# ESC.net
KiCad netlist of a schematic drawn in Altium Designer
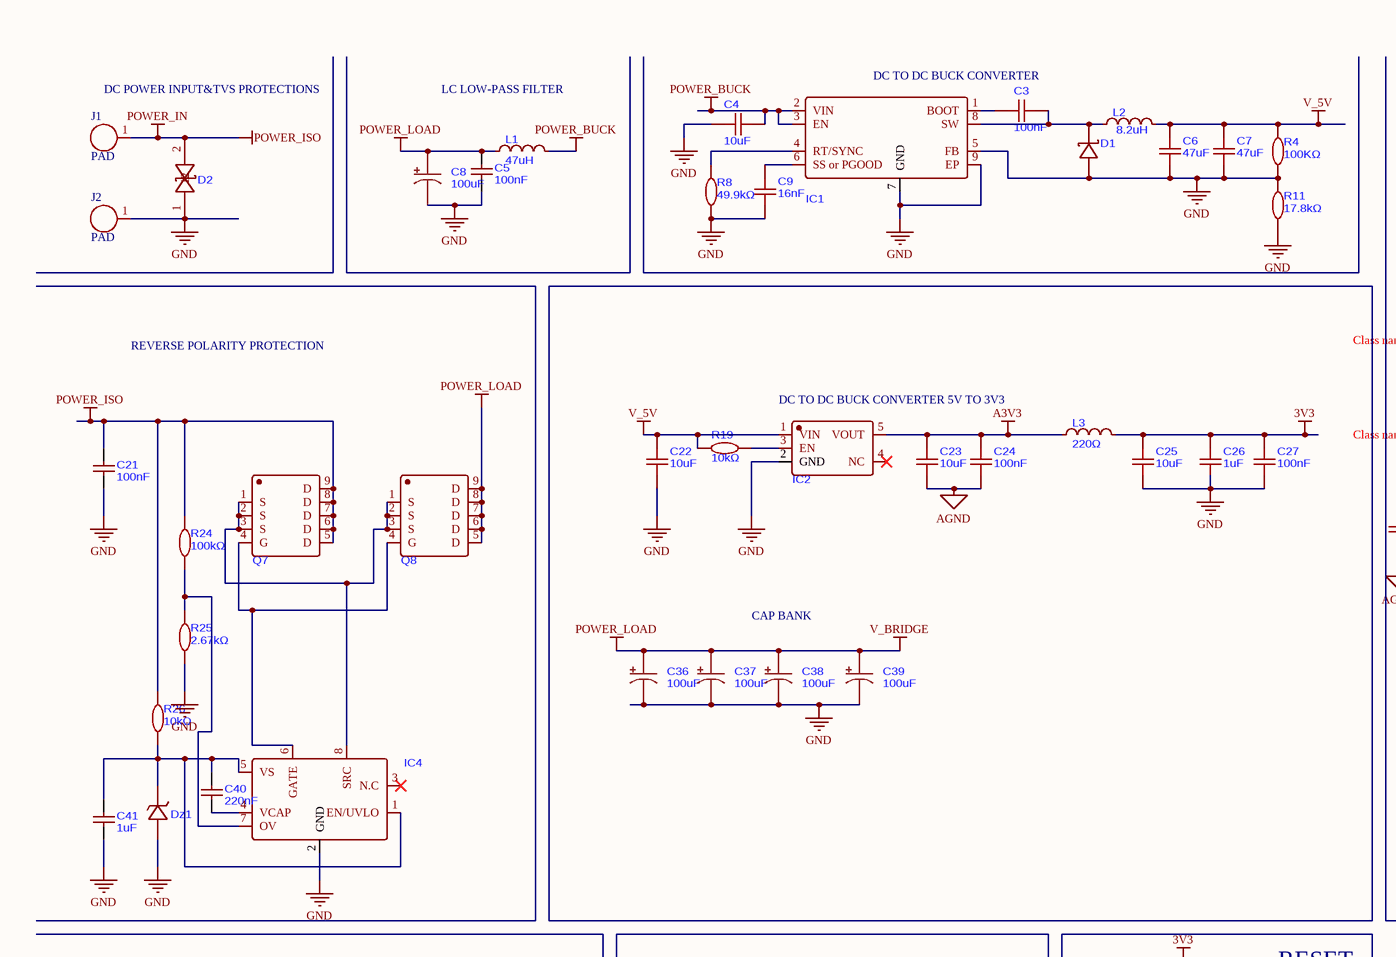
[diagram p0: ESC.SchDoc, top left]
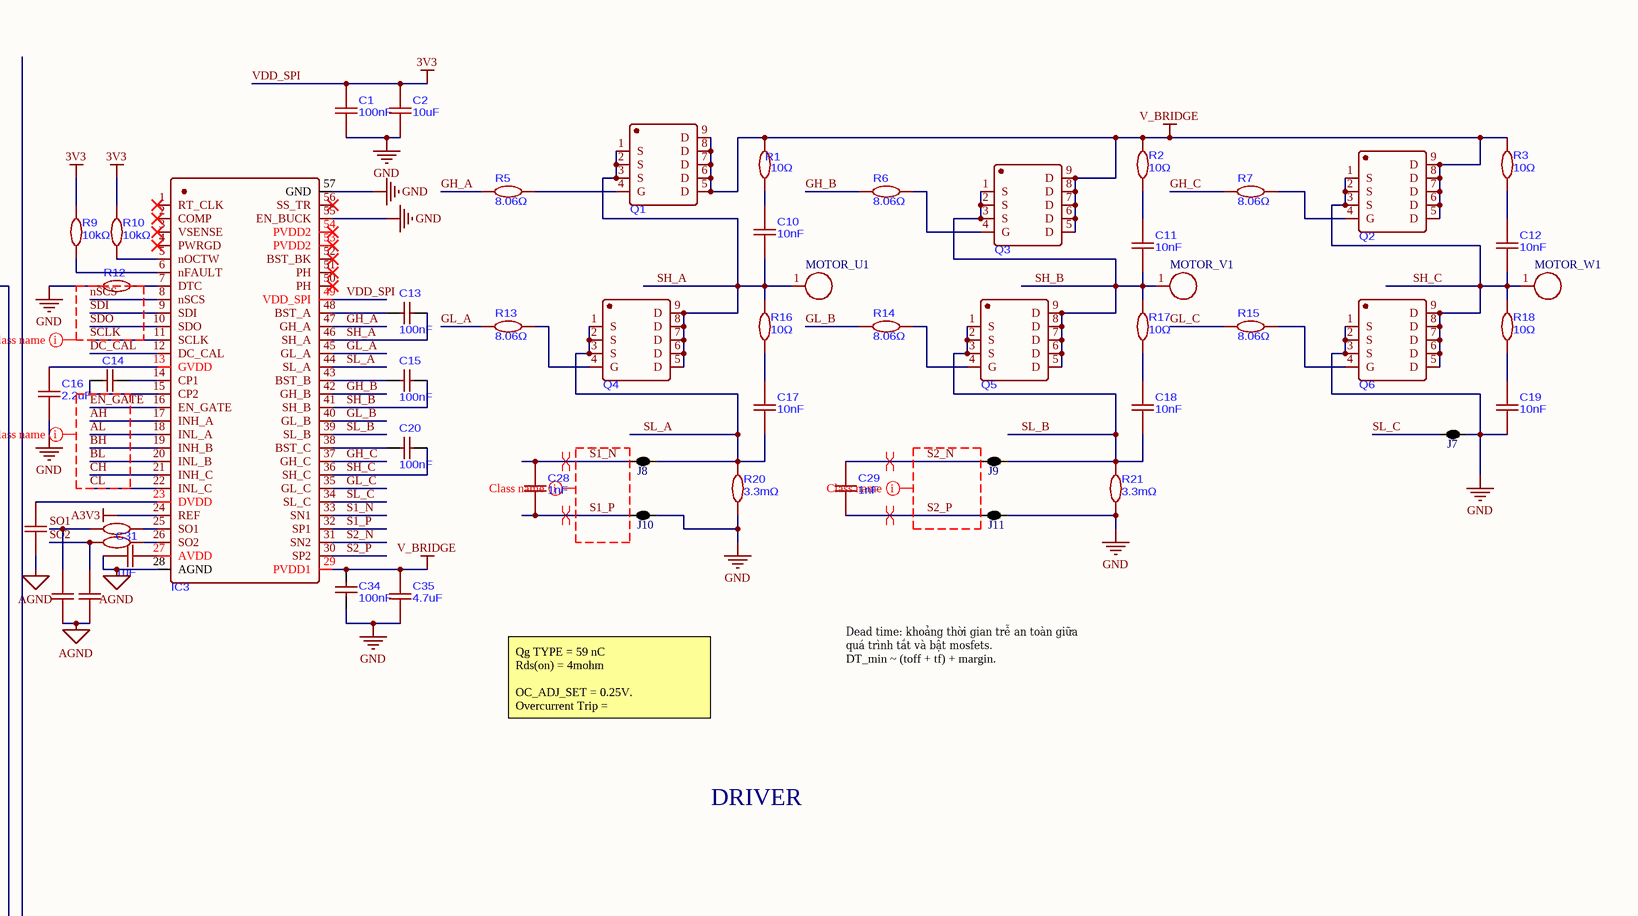
[diagram p1: ESC.SchDoc, top right]
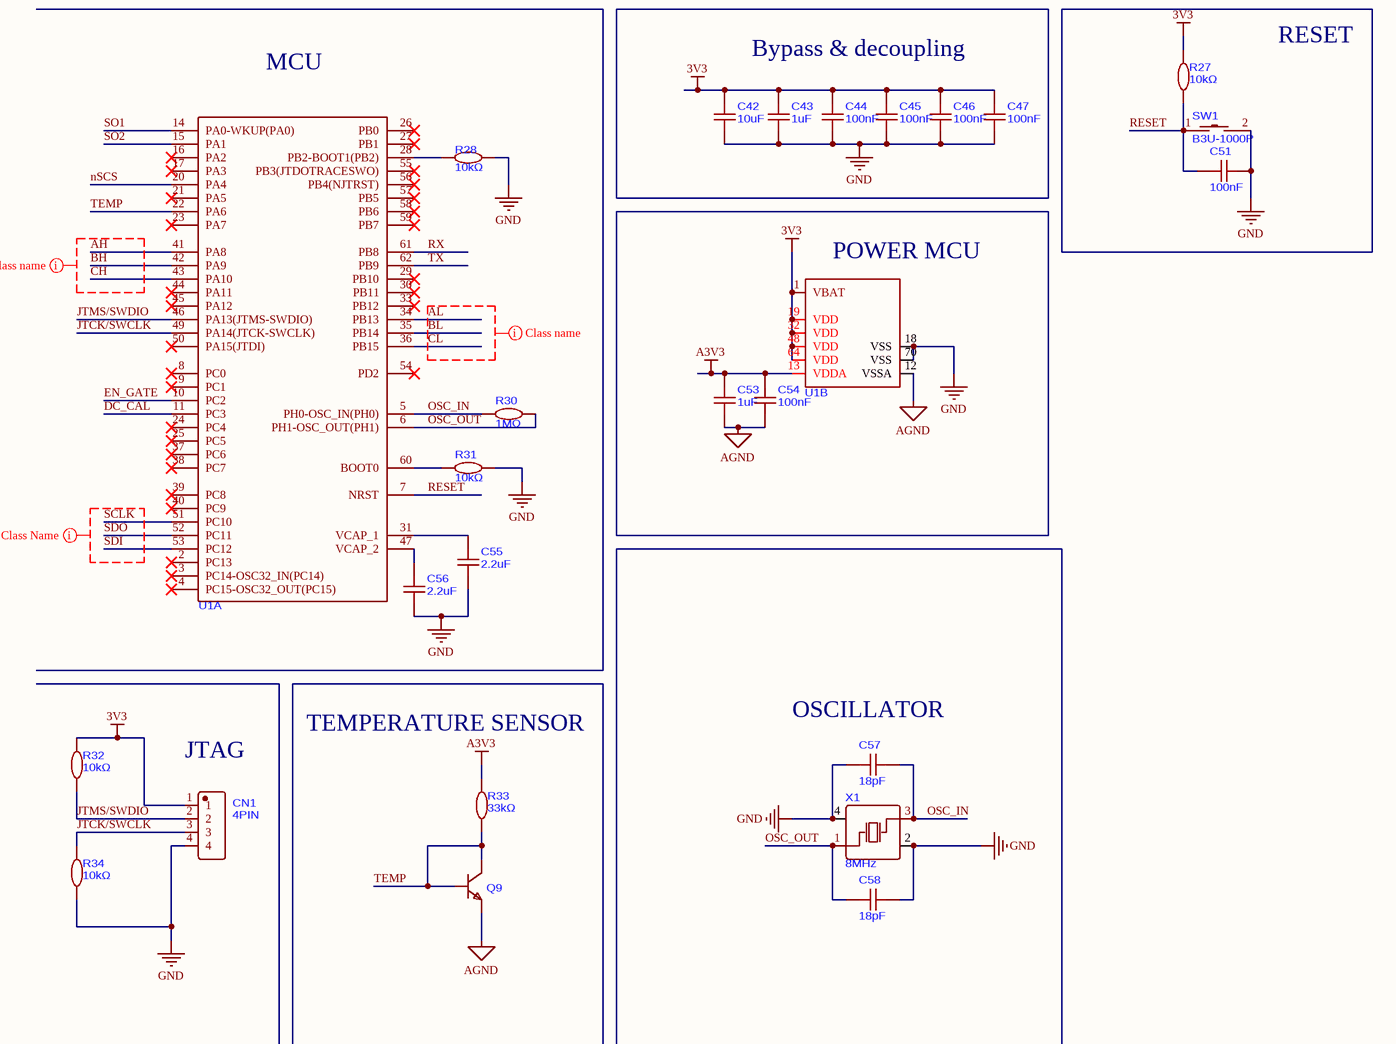
[diagram p2: ESC.SchDoc, bottom left]
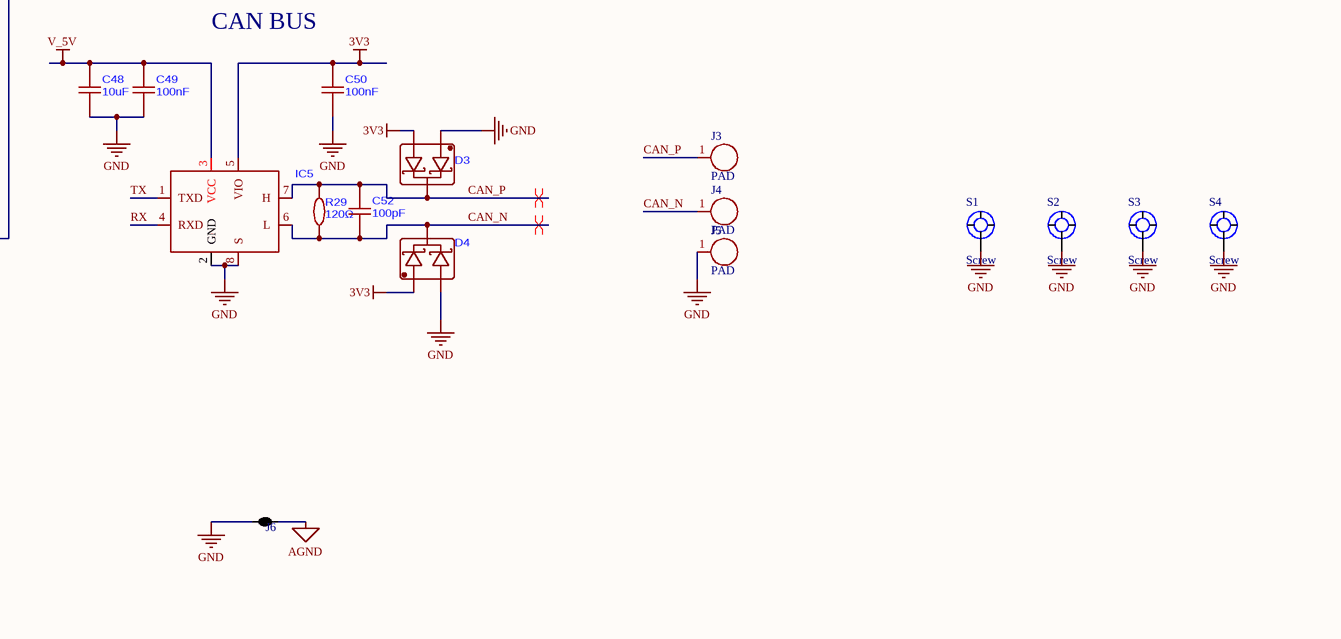
[diagram p3: ESC.SchDoc, bottom right]

(export (version "E")
  (design (tool "Eeschema 10.0.6"))
  (components
    (comp (ref "C1")
      (value "100nF")
      (footprint "C0603")
      (description "100nF ±10% 50V Ceramic Capacitor X7R 0603")
      (libsource (lib "ESC") (part "CC0603KRX7R9BB104"))
    )
    (comp (ref "C2")
      (value "10uF")
      (footprint "C0603")
      (description "10uF ±10% 10V Ceramic Capacitor X5R 0603")
      (libsource (lib "ESC") (part "CL10A106KP8NNNC"))
    )
    (comp (ref "C3")
      (value "100nF")
      (footprint "C0603")
      (description "100nF ±10% 50V Ceramic Capacitor X7R 0603")
      (libsource (lib "ESC") (part "CC0603KRX7R9BB104"))
    )
    (comp (ref "C4")
      (value "10uF")
      (footprint "C1206")
      (description "10uF X6S ±10% 100V 1206 Ceramic Capacitors RoHS")
      (libsource (lib "ESC") (part "C3216X6S2A106KT0A0E"))
    )
    (comp (ref "C5")
      (value "100nF")
      (footprint "C0805")
      (description "100nF ±10% 100V Ceramic Capacitor X7R 0805")
      (libsource (lib "ESC") (part "CL21B104KCFNNNE"))
    )
    (comp (ref "C6")
      (value "47uF")
      (footprint "C0603")
      (description "47uF ±20% 10V Ceramic Capacitor X5R 0805")
      (libsource (lib "ESC") (part "GRM21BR61A476ME15L_1"))
    )
    (comp (ref "C7")
      (value "47uF")
      (footprint "C0603")
      (description "47uF ±20% 10V Ceramic Capacitor X5R 0805")
      (libsource (lib "ESC") (part "GRM21BR61A476ME15L_1"))
    )
    (comp (ref "C8")
      (value "100uF")
      (footprint "CAP-SMD_BD10.0-L10.3-W10.3-FD")
      (description "100uF ±20% 100V Aluminum Electrolytic Capacitors")
      (libsource (lib "ESC") (part "EFVH100ADA101M10C0"))
    )
    (comp (ref "C9")
      (value "16nF")
      (footprint "C1206")
      (description "16nF ±5% 50V Ceramic Capacitor C0G 1206")
      (libsource (lib "ESC") (part "GRM3195C1H163JA01D"))
    )
    (comp (ref "C10")
      (value "10nF")
      (footprint "C0805")
      (description "10nF ±10% 100V Ceramic Capacitor X7R 0805")
      (libsource (lib "ESC") (part "CC0805KRX7R0BB103"))
    )
    (comp (ref "C11")
      (value "10nF")
      (footprint "C0805")
      (description "10nF ±10% 100V Ceramic Capacitor X7R 0805")
      (libsource (lib "ESC") (part "CC0805KRX7R0BB103"))
    )
    (comp (ref "C12")
      (value "10nF")
      (footprint "C0805")
      (description "10nF ±10% 100V Ceramic Capacitor X7R 0805")
      (libsource (lib "ESC") (part "CC0805KRX7R0BB103"))
    )
    (comp (ref "C13")
      (value "100nF")
      (footprint "C0805")
      (description "100nF ±10% 100V Ceramic Capacitor X7R 0805")
      (libsource (lib "ESC") (part "CL21B104KCFNNNE"))
    )
    (comp (ref "C14")
      (value "220nF")
      (footprint "C0805")
      (description "220nF ±10% 100V Ceramic Capacitor X7R 0805")
      (libsource (lib "ESC") (part "CC0805KKX7R0BB224"))
    )
    (comp (ref "C15")
      (value "100nF")
      (footprint "C0805")
      (description "100nF ±10% 100V Ceramic Capacitor X7R 0805")
      (libsource (lib "ESC") (part "CL21B104KCFNNNE"))
    )
    (comp (ref "C16")
      (value "2.2uF")
      (footprint "C0603")
      (description "2.2uF X5R ±10% 25V 0603 Ceramic Capacitors RoHS")
      (libsource (lib "ESC") (part "CC0603X5R25V225KN"))
    )
    (comp (ref "C17")
      (value "10nF")
      (footprint "C0805")
      (description "10nF ±10% 100V Ceramic Capacitor X7R 0805")
      (libsource (lib "ESC") (part "CC0805KRX7R0BB103"))
    )
    (comp (ref "C18")
      (value "10nF")
      (footprint "C0805")
      (description "10nF ±10% 100V Ceramic Capacitor X7R 0805")
      (libsource (lib "ESC") (part "CC0805KRX7R0BB103"))
    )
    (comp (ref "C19")
      (value "10nF")
      (footprint "C0805")
      (description "10nF ±10% 100V Ceramic Capacitor X7R 0805")
      (libsource (lib "ESC") (part "CC0805KRX7R0BB103"))
    )
    (comp (ref "C20")
      (value "100nF")
      (footprint "C0805")
      (description "100nF ±10% 100V Ceramic Capacitor X7R 0805")
      (libsource (lib "ESC") (part "CL21B104KCFNNNE"))
    )
    (comp (ref "C21")
      (value "100nF")
      (footprint "C0805")
      (description "100nF ±10% 100V Ceramic Capacitor X7R 0805")
      (libsource (lib "ESC") (part "CL21B104KCFNNNE"))
    )
    (comp (ref "C22")
      (value "10uF")
      (footprint "C0603")
      (description "10uF ±10% 10V Ceramic Capacitor X5R 0603")
      (libsource (lib "ESC") (part "CL10A106KP8NNNC"))
    )
    (comp (ref "C23")
      (value "10uF")
      (footprint "C0603")
      (description "10uF ±10% 10V Ceramic Capacitor X5R 0603")
      (libsource (lib "ESC") (part "CL10A106KP8NNNC"))
    )
    (comp (ref "C24")
      (value "100nF")
      (footprint "C0603")
      (description "100nF ±10% 50V Ceramic Capacitor X7R 0603")
      (libsource (lib "ESC") (part "CC0603KRX7R9BB104"))
    )
    (comp (ref "C25")
      (value "10uF")
      (footprint "C0603")
      (description "10uF ±10% 10V Ceramic Capacitor X5R 0603")
      (libsource (lib "ESC") (part "CL10A106KP8NNNC"))
    )
    (comp (ref "C26")
      (value "1uF")
      (footprint "C0603")
      (description "1uF ±10% 25V Ceramic Capacitor X7R 0603")
      (libsource (lib "ESC") (part "CL10B105KA8NNNC"))
    )
    (comp (ref "C27")
      (value "100nF")
      (footprint "C0603")
      (description "100nF ±10% 50V Ceramic Capacitor X7R 0603")
      (libsource (lib "ESC") (part "CC0603KRX7R9BB104"))
    )
    (comp (ref "C28")
      (value "1nF")
      (footprint "C0603")
      (description "1nF ±10% 50V Ceramic Capacitor X7R 0603")
      (libsource (lib "ESC") (part "CC0603KRX7R9BB102"))
    )
    (comp (ref "C29")
      (value "1nF")
      (footprint "C0603")
      (description "1nF ±10% 50V Ceramic Capacitor X7R 0603")
      (libsource (lib "ESC") (part "CC0603KRX7R9BB102"))
    )
    (comp (ref "C30")
      (value "1uF")
      (footprint "C0603")
      (description "1uF ±10% 25V Ceramic Capacitor X7R 0603")
      (libsource (lib "ESC") (part "CL10B105KA8NNNC"))
    )
    (comp (ref "C31")
      (value "1uF")
      (footprint "C0603")
      (description "1uF ±10% 25V Ceramic Capacitor X7R 0603")
      (libsource (lib "ESC") (part "CL10B105KA8NNNC"))
    )
    (comp (ref "C32")
      (value "2.2uF")
      (footprint "C0603")
      (description "2.2uF X5R ±10% 25V 0603 Ceramic Capacitors RoHS")
      (libsource (lib "ESC") (part "CC0603X5R25V225KN"))
    )
    (comp (ref "C33")
      (value "2.2uF")
      (footprint "C0603")
      (description "2.2uF X5R ±10% 25V 0603 Ceramic Capacitors RoHS")
      (libsource (lib "ESC") (part "CC0603X5R25V225KN"))
    )
    (comp (ref "C34")
      (value "100nF")
      (footprint "C0805")
      (description "100nF ±10% 100V Ceramic Capacitor X7R 0805")
      (libsource (lib "ESC") (part "CL21B104KCFNNNE"))
    )
    (comp (ref "C35")
      (value "4.7uF")
      (footprint "C0805")
      (description "4.7uF ±10% 100V Ceramic Capacitor X5R 0805")
      (libsource (lib "ESC") (part "CIA0805X5R475K101MT"))
    )
    (comp (ref "C36")
      (value "100uF")
      (footprint "CAP-SMD_BD10.0-L10.3-W10.3-FD")
      (description "100uF ±20% 100V Aluminum Electrolytic Capacitors")
      (libsource (lib "ESC") (part "EFVH100ADA101M10C0"))
    )
    (comp (ref "C37")
      (value "100uF")
      (footprint "CAP-SMD_BD10.0-L10.3-W10.3-FD")
      (description "100uF ±20% 100V Aluminum Electrolytic Capacitors")
      (libsource (lib "ESC") (part "EFVH100ADA101M10C0"))
    )
    (comp (ref "C38")
      (value "100uF")
      (footprint "CAP-SMD_BD10.0-L10.3-W10.3-FD")
      (description "100uF ±20% 100V Aluminum Electrolytic Capacitors")
      (libsource (lib "ESC") (part "EFVH100ADA101M10C0"))
    )
    (comp (ref "C39")
      (value "100uF")
      (footprint "CAP-SMD_BD10.0-L10.3-W10.3-FD")
      (description "100uF ±20% 100V Aluminum Electrolytic Capacitors")
      (libsource (lib "ESC") (part "EFVH100ADA101M10C0"))
    )
    (comp (ref "C40")
      (value "220nF")
      (footprint "C0603")
      (description "220nF ±10% 100V Ceramic Capacitor X7S 0603")
      (libsource (lib "ESC") (part "CGA0603X7S224K101JT"))
    )
    (comp (ref "C41")
      (value "1uF")
      (footprint "C0603")
      (description "1uF ±10% 100V Ceramic Capacitor X7T 0603")
      (libsource (lib "ESC") (part "GRM188D72A105KE01D"))
    )
    (comp (ref "C42")
      (value "10uF")
      (footprint "C0603")
      (description "10uF ±10% 10V Ceramic Capacitor X5R 0603")
      (libsource (lib "ESC") (part "CL10A106KP8NNNC"))
    )
    (comp (ref "C43")
      (value "1uF")
      (footprint "C0603")
      (description "1uF ±10% 25V Ceramic Capacitor X7R 0603")
      (libsource (lib "ESC") (part "CL10B105KA8NNNC"))
    )
    (comp (ref "C44")
      (value "100nF")
      (footprint "C0603")
      (description "100nF ±10% 50V Ceramic Capacitor X7R 0603")
      (libsource (lib "ESC") (part "CC0603KRX7R9BB104"))
    )
    (comp (ref "C45")
      (value "100nF")
      (footprint "C0603")
      (description "100nF ±10% 50V Ceramic Capacitor X7R 0603")
      (libsource (lib "ESC") (part "CC0603KRX7R9BB104"))
    )
    (comp (ref "C46")
      (value "100nF")
      (footprint "C0603")
      (description "100nF ±10% 50V Ceramic Capacitor X7R 0603")
      (libsource (lib "ESC") (part "CC0603KRX7R9BB104"))
    )
    (comp (ref "C47")
      (value "100nF")
      (footprint "C0603")
      (description "100nF ±10% 50V Ceramic Capacitor X7R 0603")
      (libsource (lib "ESC") (part "CC0603KRX7R9BB104"))
    )
    (comp (ref "C48")
      (value "10uF")
      (footprint "C0603")
      (description "10uF ±10% 10V Ceramic Capacitor X5R 0603")
      (libsource (lib "ESC") (part "CL10A106KP8NNNC"))
    )
    (comp (ref "C49")
      (value "100nF")
      (footprint "C0603")
      (description "100nF ±10% 50V Ceramic Capacitor X7R 0603")
      (libsource (lib "ESC") (part "CC0603KRX7R9BB104"))
    )
    (comp (ref "C50")
      (value "100nF")
      (footprint "C0603")
      (description "100nF ±10% 50V Ceramic Capacitor X7R 0603")
      (libsource (lib "ESC") (part "CC0603KRX7R9BB104"))
    )
    (comp (ref "C51")
      (value "100nF")
      (footprint "C0603")
      (description "100nF ±10% 50V Ceramic Capacitor X7R 0603")
      (libsource (lib "ESC") (part "CC0603KRX7R9BB104"))
    )
    (comp (ref "C52")
      (value "100pF")
      (footprint "C0603")
      (description "100pF ±5% 50V Ceramic Capacitor C0G 0603")
      (libsource (lib "ESC") (part "CL10C101JB8NNNC"))
    )
    (comp (ref "C53")
      (value "1uF")
      (footprint "C0603")
      (description "1uF ±10% 25V Ceramic Capacitor X7R 0603")
      (libsource (lib "ESC") (part "CL10B105KA8NNNC"))
    )
    (comp (ref "C54")
      (value "100nF")
      (footprint "C0603")
      (description "100nF ±10% 50V Ceramic Capacitor X7R 0603")
      (libsource (lib "ESC") (part "CC0603KRX7R9BB104"))
    )
    (comp (ref "C55")
      (value "2.2uF")
      (footprint "C0603")
      (description "2.2uF X5R ±10% 25V 0603 Ceramic Capacitors RoHS")
      (libsource (lib "ESC") (part "CC0603X5R25V225KN"))
    )
    (comp (ref "C56")
      (value "2.2uF")
      (footprint "C0603")
      (description "2.2uF X5R ±10% 25V 0603 Ceramic Capacitors RoHS")
      (libsource (lib "ESC") (part "CC0603X5R25V225KN"))
    )
    (comp (ref "C57")
      (value "18pF")
      (footprint "C0603")
      (description "18pF ±5% 50V Ceramic Capacitor C0G 0603")
      (libsource (lib "ESC") (part "CL10C180JB8NNNC"))
    )
    (comp (ref "C58")
      (value "18pF")
      (footprint "C0603")
      (description "18pF ±5% 50V Ceramic Capacitor C0G 0603")
      (libsource (lib "ESC") (part "CL10C180JB8NNNC"))
    )
    (comp (ref "CN1")
      (value "4PIN")
      (footprint "HDR-TH_4P-HX-PH254-01-04-Z-L11.5")
      (libsource (lib "ESC") (part "HX PH254-01-04-Z-L11.5 STRAIGHT PIN HEADER"))
    )
    (comp (ref "D1")
      (value "DIODE SCHOTTKY 100V DO-214AB")
      (footprint "SMC_L7.1-W6.2-LS8.1-RD")
      (description "Diode 100V 3A Surface Mount DO-214AB")
      (libsource (lib "ESC") (part "MBRS3100T3G"))
    )
    (comp (ref "D2")
      (value "TVS DIODE 54VWM 87.1VC DO-214AB(SMCJ)")
      (footprint "SMB_L4.6-W3.6-LS5.3-BI")
      (description "87.1VC Clamp 17.2A Ipp TVS DIODE DO-214AB(SMCJ)")
      (libsource (lib "ESC") (part "VISHAY SMCJ54A-E3/57T"))
    )
    (comp (ref "D3")
      (value "DIODE ARR SCHOTTKY 30V SOT-23")
      (footprint "SOT-23-3_L2.9-W1.3-P1.90-LS2.4-BR")
      (description "600mA 30V 1 Pair Common Cathode 1V@100mA 200mA SOT-23 Single Diodes RoHS")
      (libsource (lib "ESC") (part "BAT54C_C916424"))
    )
    (comp (ref "D4")
      (value "DIODE ARR SCHOTTKY 30V SOT-23")
      (footprint "SOT-23-3_L2.9-W1.3-P1.90-LS2.4-BR")
      (description "600mA 30V 1 Pair Common Cathode 1V@100mA 200mA SOT-23 Single Diodes RoHS")
      (libsource (lib "ESC") (part "BAT54C_C916424"))
    )
    (comp (ref "Dz1")
      (value "DIODE ZENER 56V 500mW SOD-123W")
      (footprint "SOD-123_L2.8-W1.8-LS3.7-RD")
      (description "Zener Diode Independent 56V 500mW Surface Mount SOD-123W")
      (libsource (lib "ESC") (part "BZT52C56"))
    )
    (comp (ref "IC1")
      (value "60V 3A Step-Down Converter")
      (footprint "SOIC-8_L4.9-W3.9-P1.27-LS6.0-BL-EP2.3")
      (libsource (lib "ESC") (part "LMR16030SDDAR"))
    )
    (comp (ref "IC2")
      (value "500mA Low-Noise LDo Voltage Regulator")
      (footprint "SOT-23-5_L2.9-W1.6-P0.95-LS2.8-BR")
      (description "3.3V 16V Positive Fixed SOT-23-5 Voltage Regulators - Linear, Low Drop Out (LDO) Regulators RoHS")
      (libsource (lib "ESC") (part "SPX3819M5-L-3-3"))
    )
    (comp (ref "IC3")
      (value "DRV8301 Three-Phase Gate Driver With Dual Current Shunt Amplifiers and Buck Regulator")
      (footprint "HTSSOP-56_L14.0-W6.0-P0.50-LS8.1-BL-EP")
      (description "MOSFET 1.7A 2.3A HTSSOP-56-EP-6mm Motor Drivers, Controllers RoHS")
      (libsource (lib "ESC") (part "DRV8301DCA"))
    )
    (comp (ref "IC4")
      (value "TSOT-23-8 OR Controllers, Ideal Diodes RoHS")
      (footprint "SOT-23-8_L2.9-W1.6-P0.65-LS2.8-BL")
      (libsource (lib "ESC") (part "LM74502DDFR"))
    )
    (comp (ref "IC5")
      (value "High-speed CAN transceiver")
      (footprint "SOIC-8_L4.9-W3.9-P1.27-LS6.0-BL")
      (description "4.5V~5.5V CAN FD Transceiver SOIC-8-150mil Drivers, Receivers, Transceivers RoHS")
      (libsource (lib "ESC") (part "TJA1051T/3/1J"))
    )
    (comp (ref "J1") (value "PAD") (footprint "PAD") (libsource (lib "ESC") (part "PAD")))
    (comp (ref "J2") (value "PAD") (footprint "PAD") (libsource (lib "ESC") (part "PAD")))
    (comp (ref "J3") (value "PAD") (footprint "PAD") (libsource (lib "ESC") (part "PAD")))
    (comp (ref "J4") (value "PAD") (footprint "PAD") (libsource (lib "ESC") (part "PAD")))
    (comp (ref "J5") (value "PAD") (footprint "PAD") (libsource (lib "ESC") (part "PAD")))
    (comp (ref "J6")
      (value "2 way net tie junction")
      (footprint "2way_HP")
      (libsource (lib "ESC") (part "2way"))
    )
    (comp (ref "J7")
      (value "2 way net tie junction")
      (footprint "2way_LP")
      (libsource (lib "ESC") (part "2way"))
    )
    (comp (ref "J8")
      (value "2 way net tie junction")
      (footprint "2way_LP")
      (libsource (lib "ESC") (part "2way"))
    )
    (comp (ref "J9")
      (value "2 way net tie junction")
      (footprint "2way_LP")
      (libsource (lib "ESC") (part "2way"))
    )
    (comp (ref "J10")
      (value "2 way net tie junction")
      (footprint "2way_LP")
      (libsource (lib "ESC") (part "2way"))
    )
    (comp (ref "J11")
      (value "2 way net tie junction")
      (footprint "2way_LP")
      (libsource (lib "ESC") (part "2way"))
    )
    (comp (ref "L1")
      (value "47uH")
      (footprint "IND-SMD_L12.3-W12.3")
      (description "2.5A 47uH 4.6A 100mΩ Magnetic Shielded Inductor ±20% SMD,12.3x12.3mm Fixed Inductors RoHS")
      (libsource (lib "ESC") (part "SMDRI127-470MT"))
    )
    (comp (ref "L2")
      (value "8.2uH")
      (footprint "IND-SMD_L7.0-W6.6_FXL0630")
      (description "5A 8.2uH 6A 60mΩ Molded Inductor ±20% SMD,7x6.6mm Fixed Inductors RoHS")
      (libsource (lib "ESC") (part "FXL0630-8R2-M"))
    )
    (comp (ref "L3")
      (value "220Ω")
      (footprint "C0805")
      (description "220Ω@100MHz 1 Line Ferrite Bead 0805 2A 45mΩ")
      (libsource (lib "ESC") (part "BLM21PG221SN1D"))
    )
    (comp (ref "MOTOR_U1") (value "PAD") (footprint "PAD") (libsource (lib "ESC") (part "PAD")))
    (comp (ref "MOTOR_V1") (value "PAD") (footprint "PAD") (libsource (lib "ESC") (part "PAD")))
    (comp (ref "MOTOR_W1") (value "PAD") (footprint "PAD") (libsource (lib "ESC") (part "PAD")))
    (comp (ref "Q1")
      (value "MOSFET N-CH 80V 100A SOP-8-Advance")
      (footprint "SOP-8_L5.0-W5.0-P1.27-LS6.0_TPH4R008NH-L1Q")
      (description "N-Channel 80V 100A 78W SOP-8-Advance")
      (libsource (lib "ESC") (part "TPH4R008NH,L1Q(M"))
    )
    (comp (ref "Q2")
      (value "MOSFET N-CH 80V 100A SOP-8-Advance")
      (footprint "SOP-8_L5.0-W5.0-P1.27-LS6.0_TPH4R008NH-L1Q")
      (description "N-Channel 80V 100A 78W SOP-8-Advance")
      (libsource (lib "ESC") (part "TPH4R008NH,L1Q(M"))
    )
    (comp (ref "Q3")
      (value "MOSFET N-CH 80V 100A SOP-8-Advance")
      (footprint "SOP-8_L5.0-W5.0-P1.27-LS6.0_TPH4R008NH-L1Q")
      (description "N-Channel 80V 100A 78W SOP-8-Advance")
      (libsource (lib "ESC") (part "TPH4R008NH,L1Q(M"))
    )
    (comp (ref "Q4")
      (value "MOSFET N-CH 80V 100A SOP-8-Advance")
      (footprint "SOP-8_L5.0-W5.0-P1.27-LS6.0_TPH4R008NH-L1Q")
      (description "N-Channel 80V 100A 78W SOP-8-Advance")
      (libsource (lib "ESC") (part "TPH4R008NH,L1Q(M"))
    )
    (comp (ref "Q5")
      (value "MOSFET N-CH 80V 100A SOP-8-Advance")
      (footprint "SOP-8_L5.0-W5.0-P1.27-LS6.0_TPH4R008NH-L1Q")
      (description "N-Channel 80V 100A 78W SOP-8-Advance")
      (libsource (lib "ESC") (part "TPH4R008NH,L1Q(M"))
    )
    (comp (ref "Q6")
      (value "MOSFET N-CH 80V 100A SOP-8-Advance")
      (footprint "SOP-8_L5.0-W5.0-P1.27-LS6.0_TPH4R008NH-L1Q")
      (description "N-Channel 80V 100A 78W SOP-8-Advance")
      (libsource (lib "ESC") (part "TPH4R008NH,L1Q(M"))
    )
    (comp (ref "Q7")
      (value "MOSFET N-CH 80V 100A SOP-8-Advance")
      (footprint "SOP-8_L5.0-W5.0-P1.27-LS6.0_TPH4R008NH-L1Q")
      (description "N-Channel 80V 100A 78W SOP-8-Advance")
      (libsource (lib "ESC") (part "TPH4R008NH,L1Q(M"))
    )
    (comp (ref "Q8")
      (value "MOSFET N-CH 80V 100A SOP-8-Advance")
      (footprint "SOP-8_L5.0-W5.0-P1.27-LS6.0_TPH4R008NH-L1Q")
      (description "N-Channel 80V 100A 78W SOP-8-Advance")
      (libsource (lib "ESC") (part "TPH4R008NH,L1Q(M"))
    )
    (comp (ref "Q9")
      (value "TRANS NPN 40V 200mA SOT-416")
      (footprint "SC-75-3_L1.6-W0.8-P1.00-LS1.6-BR")
      (description "Bipolar (BJT) Transistor NPN 40V 200mA 300MHz 200mW Surface Mount SOT-416")
      (libsource (lib "ESC") (part "MMBT3904TT1G"))
    )
    (comp (ref "R1")
      (value "10Ω")
      (footprint "R0805")
      (description "10Ω 500mW Thick Film Resistor ±100ppm/℃ ±1% 0805 Chip Resistor - Surface Mount RoHS")
      (libsource (lib "ESC") (part "CRCW080510R0FKEAHP"))
    )
    (comp (ref "R2")
      (value "10Ω")
      (footprint "R0805")
      (description "10Ω 500mW Thick Film Resistor ±100ppm/℃ ±1% 0805 Chip Resistor - Surface Mount RoHS")
      (libsource (lib "ESC") (part "CRCW080510R0FKEAHP"))
    )
    (comp (ref "R3")
      (value "10Ω")
      (footprint "R0805")
      (description "10Ω 500mW Thick Film Resistor ±100ppm/℃ ±1% 0805 Chip Resistor - Surface Mount RoHS")
      (libsource (lib "ESC") (part "CRCW080510R0FKEAHP"))
    )
    (comp (ref "R4")
      (value "100KΩ")
      (footprint "R0603")
      (description "100mW 100kΩ 75V Thick Film Resistor ±100ppm/℃ ±1% 0603 Chip Resistor - Surface Mount RoHS")
      (libsource (lib "ESC") (part "RC0603FR-07100KL"))
    )
    (comp (ref "R5")
      (value "8.06Ω")
      (footprint "R1206")
      (description "8.06Ω ±1% 250mW 1206 Thick Film Resistor")
      (libsource (lib "ESC") (part "FRC1206F8R06TS"))
    )
    (comp (ref "R6")
      (value "8.06Ω")
      (footprint "R1206")
      (description "8.06Ω ±1% 250mW 1206 Thick Film Resistor")
      (libsource (lib "ESC") (part "FRC1206F8R06TS"))
    )
    (comp (ref "R7")
      (value "8.06Ω")
      (footprint "R1206")
      (description "8.06Ω ±1% 250mW 1206 Thick Film Resistor")
      (libsource (lib "ESC") (part "FRC1206F8R06TS"))
    )
    (comp (ref "R8")
      (value "49.9kΩ")
      (footprint "R0603")
      (description "100mW 49.9kΩ 75V Thick Film Resistor ±100ppm/℃ ±1% 0603 Chip Resistor - Surface Mount RoHS")
      (libsource (lib "ESC") (part "RC0603FR-0749K9L"))
    )
    (comp (ref "R9")
      (value "10kΩ")
      (footprint "R0603")
      (description "100mW 10kΩ 75V ±100ppm/℃ Thick Film Resistor ±1% 0603 Chip Resistor - Surface Mount ROHS")
      (libsource (lib "ESC") (part "RC0603FR-0710KL"))
    )
    (comp (ref "R10")
      (value "10kΩ")
      (footprint "R0603")
      (description "100mW 10kΩ 75V ±100ppm/℃ Thick Film Resistor ±1% 0603 Chip Resistor - Surface Mount ROHS")
      (libsource (lib "ESC") (part "RC0603FR-0710KL"))
    )
    (comp (ref "R11")
      (value "17.8kΩ")
      (footprint "R0603")
      (description "17.8kΩ ±1% 100mW 0603 Thick Film Resistor")
      (libsource (lib "ESC") (part "0603WAF1782T5E"))
    )
    (comp (ref "R12")
      (value "24.9KΩ")
      (footprint "R0603")
      (description "24.9kΩ ±1% 100mW 0603 Thick Film Resistor")
      (libsource (lib "ESC") (part "FRC0603F2492TS"))
    )
    (comp (ref "R13")
      (value "8.06Ω")
      (footprint "R1206")
      (description "8.06Ω ±1% 250mW 1206 Thick Film Resistor")
      (libsource (lib "ESC") (part "FRC1206F8R06TS"))
    )
    (comp (ref "R14")
      (value "8.06Ω")
      (footprint "R1206")
      (description "8.06Ω ±1% 250mW 1206 Thick Film Resistor")
      (libsource (lib "ESC") (part "FRC1206F8R06TS"))
    )
    (comp (ref "R15")
      (value "8.06Ω")
      (footprint "R1206")
      (description "8.06Ω ±1% 250mW 1206 Thick Film Resistor")
      (libsource (lib "ESC") (part "FRC1206F8R06TS"))
    )
    (comp (ref "R16")
      (value "10Ω")
      (footprint "R0805")
      (description "10Ω 500mW Thick Film Resistor ±100ppm/℃ ±1% 0805 Chip Resistor - Surface Mount RoHS")
      (libsource (lib "ESC") (part "CRCW080510R0FKEAHP"))
    )
    (comp (ref "R17")
      (value "10Ω")
      (footprint "R0805")
      (description "10Ω 500mW Thick Film Resistor ±100ppm/℃ ±1% 0805 Chip Resistor - Surface Mount RoHS")
      (libsource (lib "ESC") (part "CRCW080510R0FKEAHP"))
    )
    (comp (ref "R18")
      (value "10Ω")
      (footprint "R0805")
      (description "10Ω 500mW Thick Film Resistor ±100ppm/℃ ±1% 0805 Chip Resistor - Surface Mount RoHS")
      (libsource (lib "ESC") (part "CRCW080510R0FKEAHP"))
    )
    (comp (ref "R19")
      (value "10kΩ")
      (footprint "R0603")
      (description "100mW 10kΩ 75V ±100ppm/℃ Thick Film Resistor ±1% 0603 Chip Resistor - Surface Mount ROHS")
      (libsource (lib "ESC") (part "RC0603FR-0710KL"))
    )
    (comp (ref "R20")
      (value "3.3mΩ")
      (footprint "R2512")
      (description "3.3mΩ 3W Current Sense Resistor ±1% ±150ppm/℃ 2512 Chip Resistor - Surface Mount RoHS")
      (libsource (lib "ESC") (part "WSLP25123L300FEA"))
    )
    (comp (ref "R21")
      (value "3.3mΩ")
      (footprint "R2512")
      (description "3.3mΩ 3W Current Sense Resistor ±1% ±150ppm/℃ 2512 Chip Resistor - Surface Mount RoHS")
      (libsource (lib "ESC") (part "WSLP25123L300FEA"))
    )
    (comp (ref "R22")
      (value "56Ω")
      (footprint "R0603")
      (description "56Ω ±1% 100mW 0603 Thick Film Resistor")
      (libsource (lib "ESC") (part "FRC0603F56R0TS"))
    )
    (comp (ref "R23")
      (value "56Ω")
      (footprint "R0603")
      (description "56Ω ±1% 100mW 0603 Thick Film Resistor")
      (libsource (lib "ESC") (part "FRC0603F56R0TS"))
    )
    (comp (ref "R24")
      (value "100kΩ")
      (footprint "R0603")
      (description "100mW 10kΩ 75V ±100ppm/℃ Thick Film Resistor ±1% 0603 Chip Resistor - Surface Mount ROHS")
      (libsource (lib "ESC") (part "RC0603FR-0710KL"))
    )
    (comp (ref "R25")
      (value "2.67kΩ")
      (footprint "R0603")
      (description "100mW 10kΩ 75V ±100ppm/℃ Thick Film Resistor ±1% 0603 Chip Resistor - Surface Mount ROHS")
      (libsource (lib "ESC") (part "RC0603FR-0710KL"))
    )
    (comp (ref "R26")
      (value "10kΩ")
      (footprint "R0603")
      (description "100mW 10kΩ 75V ±100ppm/℃ Thick Film Resistor ±1% 0603 Chip Resistor - Surface Mount ROHS")
      (libsource (lib "ESC") (part "RC0603FR-0710KL"))
    )
    (comp (ref "R27")
      (value "10kΩ")
      (footprint "R0603")
      (description "100mW 10kΩ 75V ±100ppm/℃ Thick Film Resistor ±1% 0603 Chip Resistor - Surface Mount ROHS")
      (libsource (lib "ESC") (part "RC0603FR-0710KL"))
    )
    (comp (ref "R28")
      (value "10kΩ")
      (footprint "R0603")
      (description "100mW 10kΩ 75V ±100ppm/℃ Thick Film Resistor ±1% 0603 Chip Resistor - Surface Mount ROHS")
      (libsource (lib "ESC") (part "RC0603FR-0710KL"))
    )
    (comp (ref "R29")
      (value "120Ω")
      (footprint "R0603")
      (description "120Ω ±1% 100mW 0603 Thick Film Resistor")
      (libsource (lib "ESC") (part "0603WAF1200T5E"))
    )
    (comp (ref "R30")
      (value "1MΩ")
      (footprint "R0603")
      (description "100mW 1MΩ 75V Thick Film Resistor ±100ppm/℃ ±1% 0603 Chip Resistor - Surface Mount RoHS")
      (libsource (lib "ESC") (part "RC0603FR-071ML"))
    )
    (comp (ref "R31")
      (value "10kΩ")
      (footprint "R0603")
      (description "100mW 10kΩ 75V ±100ppm/℃ Thick Film Resistor ±1% 0603 Chip Resistor - Surface Mount ROHS")
      (libsource (lib "ESC") (part "RC0603FR-0710KL"))
    )
    (comp (ref "R32")
      (value "10kΩ")
      (footprint "R0603")
      (description "100mW 10kΩ 75V ±100ppm/℃ Thick Film Resistor ±1% 0603 Chip Resistor - Surface Mount ROHS")
      (libsource (lib "ESC") (part "RC0603FR-0710KL"))
    )
    (comp (ref "R33")
      (value "33kΩ")
      (footprint "R0603")
      (description "100mW 33kΩ 75V Thick Film Resistor ±100ppm/℃ ±1% 0603 Chip Resistor - Surface Mount RoHS")
      (libsource (lib "ESC") (part "RC0603FR-0733KL"))
    )
    (comp (ref "R34")
      (value "10kΩ")
      (footprint "R0603")
      (description "100mW 10kΩ 75V ±100ppm/℃ Thick Film Resistor ±1% 0603 Chip Resistor - Surface Mount ROHS")
      (libsource (lib "ESC") (part "RC0603FR-0710KL"))
    )
    (comp (ref "S1") (value "Screw") (footprint "Screw Hole 4mm") (libsource (lib "ESC") (part "Screw")))
    (comp (ref "S2") (value "Screw") (footprint "Screw Hole 4mm") (libsource (lib "ESC") (part "Screw")))
    (comp (ref "S3") (value "Screw") (footprint "Screw Hole 4mm") (libsource (lib "ESC") (part "Screw")))
    (comp (ref "S4") (value "Screw") (footprint "Screw Hole 4mm") (libsource (lib "ESC") (part "Screw")))
    (comp (ref "SW1")
      (value "B3U-1000P")
      (footprint "KEY-SMD_B3U-1000PM")
      (description "12V 2.5mm Round Button 3mm SPST 50mA SMD,3x2.5mm Tactile Switches ROHS")
      (libsource (lib "ESC") (part "B3U-1000P"))
    )
    (comp (ref "U1")
      (value "ARM Cortex-M4 32b MCU+FPU, 210DMIPS, up to 1MB Flash/192+4KB RAM, USB OTG HS/FS, Ethernet, 17 TIMs, 3 ADCs, 15 comm. interfaces & camera")
      (footprint "LQFP-64_L10.0-W10.0-P0.50-LS12.0-BL")
      (description "ARM Cortex-M4 32 Bit 168MHz 51 LQFP-64(10x10) Microcontrollers RoHS")
      (libsource (lib "ESC") (part "STM32F405RGT6"))
    )
    (comp (ref "X1")
      (value "8MHz")
      (footprint "OSC-SMD_4P-L5.0-W3.2-BL")
      (description "Crystal 8MHz ±10ppm 10pF 200Ω SMD5032-4P")
      (libsource (lib "ESC") (part "ABM3B-8.000MHZ-10-1-U-T"))
    )
  )
  (nets
    (net (code "1") (name "/AH") (class "Default")
      (node (ref "IC3") (pin "17") (pinfunction "INH_A_17") (pintype "passive"))
      (node (ref "U1") (pin "41") (pinfunction "PA8_41") (pintype "passive"))
    )
    (net (code "2") (name "/AL") (class "Default")
      (node (ref "IC3") (pin "18") (pinfunction "INL_A_18") (pintype "passive"))
      (node (ref "U1") (pin "34") (pinfunction "PB13_34") (pintype "passive"))
    )
    (net (code "3") (name "/BH") (class "Default")
      (node (ref "IC3") (pin "19") (pinfunction "INH_B_19") (pintype "passive"))
      (node (ref "U1") (pin "42") (pinfunction "PA9_42") (pintype "passive"))
    )
    (net (code "4") (name "/BL") (class "Default")
      (node (ref "IC3") (pin "20") (pinfunction "INL_B_20") (pintype "passive"))
      (node (ref "U1") (pin "35") (pinfunction "PB14_35") (pintype "passive"))
    )
    (net (code "5") (name "/CAN_N") (class "Default")
      (node (ref "C52") (pin "1") (pinfunction "1_1") (pintype "passive"))
      (node (ref "D4") (pin "3") (pinfunction "3_3") (pintype "passive"))
      (node (ref "IC5") (pin "6") (pinfunction "L_6") (pintype "passive"))
      (node (ref "J4") (pin "1") (pintype "passive"))
      (node (ref "R29") (pin "1") (pinfunction "1_1") (pintype "passive"))
    )
    (net (code "6") (name "/CAN_P") (class "Default")
      (node (ref "C52") (pin "2") (pinfunction "2_2") (pintype "passive"))
      (node (ref "D3") (pin "3") (pinfunction "3_3") (pintype "passive"))
      (node (ref "IC5") (pin "7") (pinfunction "H_7") (pintype "passive"))
      (node (ref "J3") (pin "1") (pintype "passive"))
      (node (ref "R29") (pin "2") (pinfunction "2_2") (pintype "passive"))
    )
    (net (code "7") (name "/CH") (class "Default")
      (node (ref "IC3") (pin "21") (pinfunction "INH_C_21") (pintype "passive"))
      (node (ref "U1") (pin "43") (pinfunction "PA10_43") (pintype "passive"))
    )
    (net (code "8") (name "/CL") (class "Default")
      (node (ref "IC3") (pin "22") (pinfunction "INL_C_22") (pintype "passive"))
      (node (ref "U1") (pin "36") (pinfunction "PB15_36") (pintype "passive"))
    )
    (net (code "9") (name "/DC_CAL") (class "Default")
      (node (ref "IC3") (pin "12") (pinfunction "DC_CAL_12") (pintype "passive"))
      (node (ref "U1") (pin "11") (pinfunction "PC3_11") (pintype "passive"))
    )
    (net (code "10") (name "/EN_GATE") (class "Default")
      (node (ref "IC3") (pin "16") (pinfunction "EN_GATE_16") (pintype "passive"))
      (node (ref "U1") (pin "10") (pinfunction "PC2_10") (pintype "passive"))
    )
    (net (code "11") (name "/GH_A") (class "Default")
      (node (ref "IC3") (pin "47") (pinfunction "GH_A_47") (pintype "passive"))
      (node (ref "R5") (pin "1") (pinfunction "1_1") (pintype "passive"))
    )
    (net (code "12") (name "/GH_B") (class "Default")
      (node (ref "IC3") (pin "42") (pinfunction "GH_B_42") (pintype "passive"))
      (node (ref "R6") (pin "1") (pinfunction "1_1") (pintype "passive"))
    )
    (net (code "13") (name "/GH_C") (class "Default")
      (node (ref "IC3") (pin "37") (pinfunction "GH_C_37") (pintype "passive"))
      (node (ref "R7") (pin "1") (pinfunction "1_1") (pintype "passive"))
    )
    (net (code "14") (name "/GL_A") (class "Default")
      (node (ref "IC3") (pin "45") (pinfunction "GL_A_45") (pintype "passive"))
      (node (ref "R13") (pin "1") (pinfunction "1_1") (pintype "passive"))
    )
    (net (code "15") (name "/GL_B") (class "Default")
      (node (ref "IC3") (pin "40") (pinfunction "GL_B_40") (pintype "passive"))
      (node (ref "R14") (pin "1") (pinfunction "1_1") (pintype "passive"))
    )
    (net (code "16") (name "/GL_C") (class "Default")
      (node (ref "IC3") (pin "35") (pinfunction "GL_C_35") (pintype "passive"))
      (node (ref "R15") (pin "1") (pinfunction "1_1") (pintype "passive"))
    )
    (net (code "17") (name "/JTCK{slash}SWCLK") (class "Default")
      (node (ref "CN1") (pin "3") (pinfunction "3_3") (pintype "passive"))
      (node (ref "R34") (pin "2") (pinfunction "2_2") (pintype "passive"))
      (node (ref "U1") (pin "49") (pinfunction "PA14(JTCK-SWCLK)_49") (pintype "passive"))
    )
    (net (code "18") (name "/JTMS{slash}SWDIO") (class "Default")
      (node (ref "CN1") (pin "2") (pinfunction "2_2") (pintype "passive"))
      (node (ref "R32") (pin "1") (pinfunction "1_1") (pintype "passive"))
      (node (ref "U1") (pin "46") (pinfunction "PA13(JTMS-SWDIO)_46") (pintype "passive"))
    )
    (net (code "19") (name "/OSC_IN") (class "Default")
      (node (ref "C57") (pin "2") (pinfunction "2_2") (pintype "passive"))
      (node (ref "R30") (pin "2") (pinfunction "2_2") (pintype "passive"))
      (node (ref "U1") (pin "5") (pinfunction "PH0-OSC_IN(PH0)_5") (pintype "passive"))
      (node (ref "X1") (pin "3") (pinfunction "OSC2_3") (pintype "passive"))
    )
    (net (code "20") (name "/OSC_OUT") (class "Default")
      (node (ref "C58") (pin "1") (pinfunction "1_1") (pintype "passive"))
      (node (ref "R30") (pin "1") (pinfunction "1_1") (pintype "passive"))
      (node (ref "U1") (pin "6") (pinfunction "PH1-OSC_OUT(PH1)_6") (pintype "passive"))
      (node (ref "X1") (pin "1") (pinfunction "OSC1_1") (pintype "passive"))
    )
    (net (code "21") (name "/RESET") (class "Default")
      (node (ref "C51") (pin "1") (pinfunction "1_1") (pintype "passive"))
      (node (ref "R27") (pin "1") (pinfunction "1_1") (pintype "passive"))
      (node (ref "SW1") (pin "1") (pinfunction "1_1") (pintype "passive"))
      (node (ref "U1") (pin "7") (pinfunction "NRST_7") (pintype "passive"))
    )
    (net (code "22") (name "/RX") (class "Default")
      (node (ref "IC5") (pin "4") (pinfunction "RXD_4") (pintype "passive"))
      (node (ref "U1") (pin "61") (pinfunction "PB8_61") (pintype "passive"))
    )
    (net (code "23") (name "/S1_N") (class "Default")
      (node (ref "C28") (pin "2") (pinfunction "2_2") (pintype "passive"))
      (node (ref "IC3") (pin "33") (pinfunction "SN1_33") (pintype "passive"))
      (node (ref "J8") (pin "1") (pinfunction "1_1") (pintype "passive"))
    )
    (net (code "24") (name "/S1_P") (class "Default")
      (node (ref "C28") (pin "1") (pinfunction "1_1") (pintype "passive"))
      (node (ref "IC3") (pin "32") (pinfunction "SP1_32") (pintype "passive"))
      (node (ref "J10") (pin "1") (pinfunction "1_1") (pintype "passive"))
    )
    (net (code "25") (name "/S2_N") (class "Default")
      (node (ref "C29") (pin "2") (pinfunction "2_2") (pintype "passive"))
      (node (ref "IC3") (pin "31") (pinfunction "SN2_31") (pintype "passive"))
      (node (ref "J9") (pin "1") (pinfunction "1_1") (pintype "passive"))
    )
    (net (code "26") (name "/S2_P") (class "Default")
      (node (ref "C29") (pin "1") (pinfunction "1_1") (pintype "passive"))
      (node (ref "IC3") (pin "30") (pinfunction "SP2_30") (pintype "passive"))
      (node (ref "J11") (pin "1") (pinfunction "1_1") (pintype "passive"))
    )
    (net (code "27") (name "/SCLK") (class "Default")
      (node (ref "IC3") (pin "11") (pinfunction "SCLK_11") (pintype "passive"))
      (node (ref "U1") (pin "51") (pinfunction "PC10_51") (pintype "passive"))
    )
    (net (code "28") (name "/SDI") (class "Default")
      (node (ref "IC3") (pin "9") (pinfunction "SDI_9") (pintype "passive"))
      (node (ref "U1") (pin "53") (pinfunction "PC12_53") (pintype "passive"))
    )
    (net (code "29") (name "/SDO") (class "Default")
      (node (ref "IC3") (pin "10") (pinfunction "SDO_10") (pintype "passive"))
      (node (ref "U1") (pin "52") (pinfunction "PC11_52") (pintype "passive"))
    )
    (net (code "30") (name "/SH_A") (class "Default")
      (node (ref "C10") (pin "1") (pinfunction "1_1") (pintype "passive"))
      (node (ref "C13") (pin "2") (pinfunction "2_2") (pintype "passive"))
      (node (ref "IC3") (pin "46") (pinfunction "SH_A_46") (pintype "passive"))
      (node (ref "MOTOR_U1") (pin "1") (pintype "passive"))
      (node (ref "Q1") (pin "1") (pinfunction "S_1") (pintype "passive"))
      (node (ref "Q1") (pin "2") (pinfunction "S_2") (pintype "passive"))
      (node (ref "Q1") (pin "3") (pinfunction "S_3") (pintype "passive"))
      (node (ref "Q4") (pin "5") (pinfunction "D_5") (pintype "passive"))
      (node (ref "Q4") (pin "6") (pinfunction "D_6") (pintype "passive"))
      (node (ref "Q4") (pin "7") (pinfunction "D_7") (pintype "passive"))
      (node (ref "Q4") (pin "8") (pinfunction "D_8") (pintype "passive"))
      (node (ref "Q4") (pin "9") (pinfunction "D_9") (pintype "passive"))
      (node (ref "R16") (pin "2") (pinfunction "2_2") (pintype "passive"))
    )
    (net (code "31") (name "/SH_B") (class "Default")
      (node (ref "C11") (pin "1") (pinfunction "1_1") (pintype "passive"))
      (node (ref "C15") (pin "2") (pinfunction "2_2") (pintype "passive"))
      (node (ref "IC3") (pin "41") (pinfunction "SH_B_41") (pintype "passive"))
      (node (ref "MOTOR_V1") (pin "1") (pintype "passive"))
      (node (ref "Q3") (pin "1") (pinfunction "S_1") (pintype "passive"))
      (node (ref "Q3") (pin "2") (pinfunction "S_2") (pintype "passive"))
      (node (ref "Q3") (pin "3") (pinfunction "S_3") (pintype "passive"))
      (node (ref "Q5") (pin "5") (pinfunction "D_5") (pintype "passive"))
      (node (ref "Q5") (pin "6") (pinfunction "D_6") (pintype "passive"))
      (node (ref "Q5") (pin "7") (pinfunction "D_7") (pintype "passive"))
      (node (ref "Q5") (pin "8") (pinfunction "D_8") (pintype "passive"))
      (node (ref "Q5") (pin "9") (pinfunction "D_9") (pintype "passive"))
      (node (ref "R17") (pin "2") (pinfunction "2_2") (pintype "passive"))
    )
    (net (code "32") (name "/SH_C") (class "Default")
      (node (ref "C12") (pin "1") (pinfunction "1_1") (pintype "passive"))
      (node (ref "C20") (pin "2") (pinfunction "2_2") (pintype "passive"))
      (node (ref "IC3") (pin "36") (pinfunction "SH_C_36") (pintype "passive"))
      (node (ref "MOTOR_W1") (pin "1") (pintype "passive"))
      (node (ref "Q2") (pin "1") (pinfunction "S_1") (pintype "passive"))
      (node (ref "Q2") (pin "2") (pinfunction "S_2") (pintype "passive"))
      (node (ref "Q2") (pin "3") (pinfunction "S_3") (pintype "passive"))
      (node (ref "Q6") (pin "5") (pinfunction "D_5") (pintype "passive"))
      (node (ref "Q6") (pin "6") (pinfunction "D_6") (pintype "passive"))
      (node (ref "Q6") (pin "7") (pinfunction "D_7") (pintype "passive"))
      (node (ref "Q6") (pin "8") (pinfunction "D_8") (pintype "passive"))
      (node (ref "Q6") (pin "9") (pinfunction "D_9") (pintype "passive"))
      (node (ref "R18") (pin "2") (pinfunction "2_2") (pintype "passive"))
    )
    (net (code "33") (name "/SL_A") (class "Default")
      (node (ref "C17") (pin "1") (pinfunction "1_1") (pintype "passive"))
      (node (ref "IC3") (pin "44") (pinfunction "SL_A_44") (pintype "passive"))
      (node (ref "J8") (pin "2") (pinfunction "2_2") (pintype "passive"))
      (node (ref "Q4") (pin "1") (pinfunction "S_1") (pintype "passive"))
      (node (ref "Q4") (pin "2") (pinfunction "S_2") (pintype "passive"))
      (node (ref "Q4") (pin "3") (pinfunction "S_3") (pintype "passive"))
      (node (ref "R20") (pin "2") (pinfunction "2_2") (pintype "passive"))
    )
    (net (code "34") (name "/SL_B") (class "Default")
      (node (ref "C18") (pin "1") (pinfunction "1_1") (pintype "passive"))
      (node (ref "IC3") (pin "39") (pinfunction "SL_B_39") (pintype "passive"))
      (node (ref "J9") (pin "2") (pinfunction "2_2") (pintype "passive"))
      (node (ref "Q5") (pin "1") (pinfunction "S_1") (pintype "passive"))
      (node (ref "Q5") (pin "2") (pinfunction "S_2") (pintype "passive"))
      (node (ref "Q5") (pin "3") (pinfunction "S_3") (pintype "passive"))
      (node (ref "R21") (pin "2") (pinfunction "2_2") (pintype "passive"))
    )
    (net (code "35") (name "/SL_C") (class "Default")
      (node (ref "IC3") (pin "34") (pinfunction "SL_C_34") (pintype "passive"))
      (node (ref "J7") (pin "1") (pinfunction "1_1") (pintype "passive"))
    )
    (net (code "36") (name "/SO1") (class "Default")
      (node (ref "C32") (pin "2") (pinfunction "2_2") (pintype "passive"))
      (node (ref "R22") (pin "2") (pinfunction "2_2") (pintype "passive"))
      (node (ref "U1") (pin "14") (pinfunction "PA0-WKUP(PA0)_14") (pintype "passive"))
    )
    (net (code "37") (name "/SO2") (class "Default")
      (node (ref "C33") (pin "2") (pinfunction "2_2") (pintype "passive"))
      (node (ref "R23") (pin "2") (pinfunction "2_2") (pintype "passive"))
      (node (ref "U1") (pin "15") (pinfunction "PA1_15") (pintype "passive"))
    )
    (net (code "38") (name "/TEMP") (class "Default")
      (node (ref "Q9") (pin "1") (pinfunction "B_1") (pintype "passive"))
      (node (ref "Q9") (pin "3") (pinfunction "C_3") (pintype "passive"))
      (node (ref "R33") (pin "1") (pinfunction "1_1") (pintype "passive"))
      (node (ref "U1") (pin "22") (pinfunction "PA6_22") (pintype "passive"))
    )
    (net (code "39") (name "/TX") (class "Default")
      (node (ref "IC5") (pin "1") (pinfunction "TXD_1") (pintype "passive"))
      (node (ref "U1") (pin "62") (pinfunction "PB9_62") (pintype "passive"))
    )
    (net (code "40") (name "/nSCS") (class "Default")
      (node (ref "IC3") (pin "8") (pinfunction "nSCS_8") (pintype "passive"))
      (node (ref "U1") (pin "20") (pinfunction "PA4_20") (pintype "passive"))
    )
    (net (code "41") (name "3V3") (class "Default")
      (node (ref "C1") (pin "2") (pinfunction "2_2") (pintype "passive"))
      (node (ref "C2") (pin "2") (pinfunction "2_2") (pintype "passive"))
      (node (ref "C25") (pin "2") (pinfunction "2_2") (pintype "passive"))
      (node (ref "C26") (pin "2") (pinfunction "2_2") (pintype "passive"))
      (node (ref "C27") (pin "2") (pinfunction "2_2") (pintype "passive"))
      (node (ref "C42") (pin "2") (pinfunction "2_2") (pintype "passive"))
      (node (ref "C43") (pin "2") (pinfunction "2_2") (pintype "passive"))
      (node (ref "C44") (pin "2") (pinfunction "2_2") (pintype "passive"))
      (node (ref "C45") (pin "2") (pinfunction "2_2") (pintype "passive"))
      (node (ref "C46") (pin "2") (pinfunction "2_2") (pintype "passive"))
      (node (ref "C47") (pin "2") (pinfunction "2_2") (pintype "passive"))
      (node (ref "C50") (pin "2") (pinfunction "2_2") (pintype "passive"))
      (node (ref "CN1") (pin "1") (pinfunction "1_1") (pintype "passive"))
      (node (ref "D3") (pin "2") (pinfunction "2_2") (pintype "passive"))
      (node (ref "D4") (pin "1") (pinfunction "1_1") (pintype "passive"))
      (node (ref "IC3") (pin "49") (pinfunction "VDD_SPI_49") (pintype "passive"))
      (node (ref "IC5") (pin "5") (pinfunction "VIO_5") (pintype "passive"))
      (node (ref "L3") (pin "2") (pinfunction "2_2") (pintype "passive"))
      (node (ref "R10") (pin "1") (pinfunction "1_1") (pintype "passive"))
      (node (ref "R27") (pin "2") (pinfunction "2_2") (pintype "passive"))
      (node (ref "R32") (pin "2") (pinfunction "2_2") (pintype "passive"))
      (node (ref "R9") (pin "2") (pinfunction "2_2") (pintype "passive"))
      (node (ref "U1") (pin "1") (pinfunction "VBAT_1") (pintype "passive"))
      (node (ref "U1") (pin "19") (pinfunction "VDD_19") (pintype "passive"))
      (node (ref "U1") (pin "32") (pinfunction "VDD_32") (pintype "passive"))
      (node (ref "U1") (pin "48") (pinfunction "VDD_48") (pintype "passive"))
      (node (ref "U1") (pin "64") (pinfunction "VDD_64") (pintype "passive"))
    )
    (net (code "42") (name "A3V3") (class "Default")
      (node (ref "C23") (pin "2") (pinfunction "2_2") (pintype "passive"))
      (node (ref "C24") (pin "2") (pinfunction "2_2") (pintype "passive"))
      (node (ref "C53") (pin "2") (pinfunction "2_2") (pintype "passive"))
      (node (ref "C54") (pin "2") (pinfunction "2_2") (pintype "passive"))
      (node (ref "IC2") (pin "5") (pinfunction "VOUT_5") (pintype "passive"))
      (node (ref "IC3") (pin "24") (pinfunction "REF_24") (pintype "passive"))
      (node (ref "L3") (pin "1") (pinfunction "1_1") (pintype "passive"))
      (node (ref "R33") (pin "2") (pinfunction "2_2") (pintype "passive"))
      (node (ref "U1") (pin "13") (pinfunction "VDDA_13") (pintype "passive"))
    )
    (net (code "43") (name "AGND") (class "Default")
      (node (ref "C23") (pin "1") (pinfunction "1_1") (pintype "passive"))
      (node (ref "C24") (pin "1") (pinfunction "1_1") (pintype "passive"))
      (node (ref "C30") (pin "1") (pinfunction "1_1") (pintype "passive"))
      (node (ref "C31") (pin "2") (pinfunction "2_2") (pintype "passive"))
      (node (ref "C32") (pin "1") (pinfunction "1_1") (pintype "passive"))
      (node (ref "C33") (pin "1") (pinfunction "1_1") (pintype "passive"))
      (node (ref "C53") (pin "1") (pinfunction "1_1") (pintype "passive"))
      (node (ref "C54") (pin "1") (pinfunction "1_1") (pintype "passive"))
      (node (ref "IC3") (pin "28") (pinfunction "AGND_28") (pintype "passive"))
      (node (ref "J6") (pin "2") (pinfunction "2_2") (pintype "passive"))
      (node (ref "Q9") (pin "2") (pinfunction "E_2") (pintype "passive"))
      (node (ref "U1") (pin "12") (pinfunction "VSSA_12") (pintype "passive"))
    )
    (net (code "44") (name "GND") (class "Default")
      (node (ref "C1") (pin "1") (pinfunction "1_1") (pintype "passive"))
      (node (ref "C16") (pin "1") (pinfunction "1_1") (pintype "passive"))
      (node (ref "C19") (pin "1") (pinfunction "1_1") (pintype "passive"))
      (node (ref "C2") (pin "1") (pinfunction "1_1") (pintype "passive"))
      (node (ref "C21") (pin "1") (pinfunction "1_1") (pintype "passive"))
      (node (ref "C22") (pin "1") (pinfunction "1_1") (pintype "passive"))
      (node (ref "C25") (pin "1") (pinfunction "1_1") (pintype "passive"))
      (node (ref "C26") (pin "1") (pinfunction "1_1") (pintype "passive"))
      (node (ref "C27") (pin "1") (pinfunction "1_1") (pintype "passive"))
      (node (ref "C34") (pin "1") (pinfunction "1_1") (pintype "passive"))
      (node (ref "C35") (pin "1") (pinfunction "1_1") (pintype "passive"))
      (node (ref "C36") (pin "2") (pinfunction "2_2") (pintype "passive"))
      (node (ref "C37") (pin "2") (pinfunction "2_2") (pintype "passive"))
      (node (ref "C38") (pin "2") (pinfunction "2_2") (pintype "passive"))
      (node (ref "C39") (pin "2") (pinfunction "2_2") (pintype "passive"))
      (node (ref "C4") (pin "2") (pinfunction "2_2") (pintype "passive"))
      (node (ref "C41") (pin "1") (pinfunction "1_1") (pintype "passive"))
      (node (ref "C42") (pin "1") (pinfunction "1_1") (pintype "passive"))
      (node (ref "C43") (pin "1") (pinfunction "1_1") (pintype "passive"))
      (node (ref "C44") (pin "1") (pinfunction "1_1") (pintype "passive"))
      (node (ref "C45") (pin "1") (pinfunction "1_1") (pintype "passive"))
      (node (ref "C46") (pin "1") (pinfunction "1_1") (pintype "passive"))
      (node (ref "C47") (pin "1") (pinfunction "1_1") (pintype "passive"))
      (node (ref "C48") (pin "1") (pinfunction "1_1") (pintype "passive"))
      (node (ref "C49") (pin "1") (pinfunction "1_1") (pintype "passive"))
      (node (ref "C5") (pin "1") (pinfunction "1_1") (pintype "passive"))
      (node (ref "C50") (pin "1") (pinfunction "1_1") (pintype "passive"))
      (node (ref "C51") (pin "2") (pinfunction "2_2") (pintype "passive"))
      (node (ref "C55") (pin "1") (pinfunction "1_1") (pintype "passive"))
      (node (ref "C56") (pin "1") (pinfunction "1_1") (pintype "passive"))
      (node (ref "C57") (pin "1") (pinfunction "1_1") (pintype "passive"))
      (node (ref "C58") (pin "2") (pinfunction "2_2") (pintype "passive"))
      (node (ref "C6") (pin "1") (pinfunction "1_1") (pintype "passive"))
      (node (ref "C7") (pin "1") (pinfunction "1_1") (pintype "passive"))
      (node (ref "C8") (pin "2") (pinfunction "2_2") (pintype "passive"))
      (node (ref "C9") (pin "1") (pinfunction "1_1") (pintype "passive"))
      (node (ref "CN1") (pin "4") (pinfunction "4_4") (pintype "passive"))
      (node (ref "D1") (pin "2") (pinfunction "A_2") (pintype "passive"))
      (node (ref "D2") (pin "1") (pinfunction "1_1") (pintype "passive"))
      (node (ref "D3") (pin "1") (pinfunction "1_1") (pintype "passive"))
      (node (ref "D4") (pin "2") (pinfunction "2_2") (pintype "passive"))
      (node (ref "Dz1") (pin "2") (pinfunction "A_2") (pintype "passive"))
      (node (ref "IC1") (pin "5") (pinfunction "FB_5") (pintype "passive"))
      (node (ref "IC1") (pin "7") (pinfunction "GND_7") (pintype "passive"))
      (node (ref "IC1") (pin "9") (pinfunction "EP_9") (pintype "passive"))
      (node (ref "IC2") (pin "2") (pinfunction "GND_2") (pintype "passive"))
      (node (ref "IC3") (pin "55") (pinfunction "EN_BUCK_55") (pintype "passive"))
      (node (ref "IC3") (pin "57") (pinfunction "GND_57") (pintype "passive"))
      (node (ref "IC4") (pin "2") (pinfunction "GND_2") (pintype "passive"))
      (node (ref "IC5") (pin "2") (pinfunction "GND_2") (pintype "passive"))
      (node (ref "IC5") (pin "8") (pinfunction "S_8") (pintype "passive"))
      (node (ref "J10") (pin "2") (pinfunction "2_2") (pintype "passive"))
      (node (ref "J11") (pin "2") (pinfunction "2_2") (pintype "passive"))
      (node (ref "J2") (pin "1") (pintype "passive"))
      (node (ref "J5") (pin "1") (pintype "passive"))
      (node (ref "J6") (pin "1") (pinfunction "1_1") (pintype "passive"))
      (node (ref "J7") (pin "2") (pinfunction "2_2") (pintype "passive"))
      (node (ref "Q6") (pin "1") (pinfunction "S_1") (pintype "passive"))
      (node (ref "Q6") (pin "2") (pinfunction "S_2") (pintype "passive"))
      (node (ref "Q6") (pin "3") (pinfunction "S_3") (pintype "passive"))
      (node (ref "R11") (pin "1") (pinfunction "1_1") (pintype "passive"))
      (node (ref "R11") (pin "2") (pinfunction "2_2") (pintype "passive"))
      (node (ref "R12") (pin "1") (pinfunction "1_1") (pintype "passive"))
      (node (ref "R20") (pin "1") (pinfunction "1_1") (pintype "passive"))
      (node (ref "R21") (pin "1") (pinfunction "1_1") (pintype "passive"))
      (node (ref "R25") (pin "1") (pinfunction "1_1") (pintype "passive"))
      (node (ref "R28") (pin "2") (pinfunction "2_2") (pintype "passive"))
      (node (ref "R31") (pin "1") (pinfunction "1_1") (pintype "passive"))
      (node (ref "R34") (pin "1") (pinfunction "1_1") (pintype "passive"))
      (node (ref "R4") (pin "1") (pinfunction "1_1") (pintype "passive"))
      (node (ref "R8") (pin "1") (pinfunction "1_1") (pintype "passive"))
      (node (ref "S1") (pin "1") (pinfunction "1_1") (pintype "passive"))
      (node (ref "S2") (pin "1") (pinfunction "1_1") (pintype "passive"))
      (node (ref "S3") (pin "1") (pinfunction "1_1") (pintype "passive"))
      (node (ref "S4") (pin "1") (pinfunction "1_1") (pintype "passive"))
      (node (ref "SW1") (pin "2") (pinfunction "2_2") (pintype "passive"))
      (node (ref "U1") (pin "18") (pinfunction "VSS_18") (pintype "passive"))
      (node (ref "U1") (pin "70") (pinfunction "VSS_70") (pintype "passive"))
      (node (ref "X1") (pin "2") (pinfunction "GND_2") (pintype "passive"))
      (node (ref "X1") (pin "4") (pinfunction "GND_4") (pintype "passive"))
    )
    (net (code "45") (name "Net-(C10-Pad2)") (class "Default")
      (node (ref "C10") (pin "2") (pinfunction "2_2") (pintype "passive"))
      (node (ref "R1") (pin "1") (pinfunction "1_1") (pintype "passive"))
    )
    (net (code "46") (name "Net-(C11-Pad2)") (class "Default")
      (node (ref "C11") (pin "2") (pinfunction "2_2") (pintype "passive"))
      (node (ref "R2") (pin "1") (pinfunction "1_1") (pintype "passive"))
    )
    (net (code "47") (name "Net-(C12-Pad2)") (class "Default")
      (node (ref "C12") (pin "2") (pinfunction "2_2") (pintype "passive"))
      (node (ref "R3") (pin "1") (pinfunction "1_1") (pintype "passive"))
    )
    (net (code "48") (name "Net-(C17-Pad2)") (class "Default")
      (node (ref "C17") (pin "2") (pinfunction "2_2") (pintype "passive"))
      (node (ref "R16") (pin "1") (pinfunction "1_1") (pintype "passive"))
    )
    (net (code "49") (name "Net-(C18-Pad2)") (class "Default")
      (node (ref "C18") (pin "2") (pinfunction "2_2") (pintype "passive"))
      (node (ref "R17") (pin "1") (pinfunction "1_1") (pintype "passive"))
    )
    (net (code "50") (name "Net-(C19-Pad2)") (class "Default")
      (node (ref "C19") (pin "2") (pinfunction "2_2") (pintype "passive"))
      (node (ref "R18") (pin "1") (pinfunction "1_1") (pintype "passive"))
    )
    (net (code "51") (name "Net-(D1-C)") (class "Default")
      (node (ref "C3") (pin "1") (pinfunction "1_1") (pintype "passive"))
      (node (ref "D1") (pin "1") (pinfunction "C_1") (pintype "passive"))
      (node (ref "IC1") (pin "8") (pinfunction "SW_8") (pintype "passive"))
      (node (ref "L2") (pin "1") (pinfunction "1_1") (pintype "passive"))
    )
    (net (code "52") (name "Net-(Dz1-K)") (class "Default")
      (node (ref "C40") (pin "2") (pinfunction "2_2") (pintype "passive"))
      (node (ref "C41") (pin "2") (pinfunction "2_2") (pintype "passive"))
      (node (ref "Dz1") (pin "1") (pinfunction "K_1") (pintype "passive"))
      (node (ref "IC4") (pin "1") (pinfunction "EN/UVLO_1") (pintype "passive"))
      (node (ref "IC4") (pin "5") (pinfunction "VS_5") (pintype "passive"))
      (node (ref "R26") (pin "1") (pinfunction "1_1") (pintype "passive"))
    )
    (net (code "53") (name "Net-(IC1-BOOT)") (class "Default")
      (node (ref "C3") (pin "2") (pinfunction "2_2") (pintype "passive"))
      (node (ref "IC1") (pin "1") (pinfunction "BOOT_1") (pintype "passive"))
    )
    (net (code "54") (name "Net-(IC1-RT{slash}SYNC)") (class "Default")
      (node (ref "IC1") (pin "4") (pinfunction "RT/SYNC_4") (pintype "passive"))
      (node (ref "R8") (pin "2") (pinfunction "2_2") (pintype "passive"))
    )
    (net (code "55") (name "Net-(IC1-SS_or_PGOOD)") (class "Default")
      (node (ref "C9") (pin "2") (pinfunction "2_2") (pintype "passive"))
      (node (ref "IC1") (pin "6") (pinfunction "SS_or_PGOOD_6") (pintype "passive"))
    )
    (net (code "56") (name "Net-(IC2-EN)") (class "Default")
      (node (ref "IC2") (pin "3") (pinfunction "EN_3") (pintype "passive"))
      (node (ref "R19") (pin "1") (pinfunction "1_1") (pintype "passive"))
    )
    (net (code "57") (name "Net-(IC3-AVDD)") (class "Default")
      (node (ref "C31") (pin "1") (pinfunction "1_1") (pintype "passive"))
      (node (ref "IC3") (pin "27") (pinfunction "AVDD_27") (pintype "passive"))
    )
    (net (code "58") (name "Net-(IC3-BST_A)") (class "Default")
      (node (ref "C13") (pin "1") (pinfunction "1_1") (pintype "passive"))
      (node (ref "IC3") (pin "48") (pinfunction "BST_A_48") (pintype "passive"))
    )
    (net (code "59") (name "Net-(IC3-BST_B)") (class "Default")
      (node (ref "C15") (pin "1") (pinfunction "1_1") (pintype "passive"))
      (node (ref "IC3") (pin "43") (pinfunction "BST_B_43") (pintype "passive"))
    )
    (net (code "60") (name "Net-(IC3-BST_C)") (class "Default")
      (node (ref "C20") (pin "1") (pinfunction "1_1") (pintype "passive"))
      (node (ref "IC3") (pin "38") (pinfunction "BST_C_38") (pintype "passive"))
    )
    (net (code "61") (name "Net-(IC3-CP1)") (class "Default")
      (node (ref "C14") (pin "2") (pinfunction "2_2") (pintype "passive"))
      (node (ref "IC3") (pin "14") (pinfunction "CP1_14") (pintype "passive"))
    )
    (net (code "62") (name "Net-(IC3-CP2)") (class "Default")
      (node (ref "C14") (pin "1") (pinfunction "1_1") (pintype "passive"))
      (node (ref "IC3") (pin "15") (pinfunction "CP2_15") (pintype "passive"))
    )
    (net (code "63") (name "Net-(IC3-DTC)") (class "Default")
      (node (ref "IC3") (pin "7") (pinfunction "DTC_7") (pintype "passive"))
      (node (ref "R12") (pin "2") (pinfunction "2_2") (pintype "passive"))
    )
    (net (code "64") (name "Net-(IC3-DVDD)") (class "Default")
      (node (ref "C30") (pin "2") (pinfunction "2_2") (pintype "passive"))
      (node (ref "IC3") (pin "23") (pinfunction "DVDD_23") (pintype "passive"))
    )
    (net (code "65") (name "Net-(IC3-GVDD)") (class "Default")
      (node (ref "C16") (pin "2") (pinfunction "2_2") (pintype "passive"))
      (node (ref "IC3") (pin "13") (pinfunction "GVDD_13") (pintype "passive"))
    )
    (net (code "66") (name "Net-(IC3-SO1)") (class "Default")
      (node (ref "IC3") (pin "25") (pinfunction "SO1_25") (pintype "passive"))
      (node (ref "R22") (pin "1") (pinfunction "1_1") (pintype "passive"))
    )
    (net (code "67") (name "Net-(IC3-SO2)") (class "Default")
      (node (ref "IC3") (pin "26") (pinfunction "SO2_26") (pintype "passive"))
      (node (ref "R23") (pin "1") (pinfunction "1_1") (pintype "passive"))
    )
    (net (code "68") (name "Net-(IC3-nFAULT)") (class "Default")
      (node (ref "IC3") (pin "6") (pinfunction "nFAULT_6") (pintype "passive"))
      (node (ref "R9") (pin "1") (pinfunction "1_1") (pintype "passive"))
    )
    (net (code "69") (name "Net-(IC3-nOCTW)") (class "Default")
      (node (ref "IC3") (pin "5") (pinfunction "nOCTW_5") (pintype "passive"))
      (node (ref "R10") (pin "2") (pinfunction "2_2") (pintype "passive"))
    )
    (net (code "70") (name "Net-(IC4-GATE)") (class "Default")
      (node (ref "IC4") (pin "6") (pinfunction "GATE_6") (pintype "passive"))
      (node (ref "Q7") (pin "4") (pinfunction "G_4") (pintype "passive"))
      (node (ref "Q8") (pin "4") (pinfunction "G_4") (pintype "passive"))
    )
    (net (code "71") (name "Net-(IC4-OV)") (class "Default")
      (node (ref "IC4") (pin "7") (pinfunction "OV_7") (pintype "passive"))
      (node (ref "R24") (pin "1") (pinfunction "1_1") (pintype "passive"))
      (node (ref "R25") (pin "2") (pinfunction "2_2") (pintype "passive"))
    )
    (net (code "72") (name "Net-(IC4-SRC)") (class "Default")
      (node (ref "IC4") (pin "8") (pinfunction "SRC_8") (pintype "passive"))
      (node (ref "Q7") (pin "1") (pinfunction "S_1") (pintype "passive"))
      (node (ref "Q7") (pin "2") (pinfunction "S_2") (pintype "passive"))
      (node (ref "Q7") (pin "3") (pinfunction "S_3") (pintype "passive"))
      (node (ref "Q8") (pin "1") (pinfunction "S_1") (pintype "passive"))
      (node (ref "Q8") (pin "2") (pinfunction "S_2") (pintype "passive"))
      (node (ref "Q8") (pin "3") (pinfunction "S_3") (pintype "passive"))
    )
    (net (code "73") (name "Net-(IC4-VCAP)") (class "Default")
      (node (ref "C40") (pin "1") (pinfunction "1_1") (pintype "passive"))
      (node (ref "IC4") (pin "4") (pinfunction "VCAP_4") (pintype "passive"))
    )
    (net (code "74") (name "Net-(Q1-G)") (class "Default")
      (node (ref "Q1") (pin "4") (pinfunction "G_4") (pintype "passive"))
      (node (ref "R5") (pin "2") (pinfunction "2_2") (pintype "passive"))
    )
    (net (code "75") (name "Net-(Q2-G)") (class "Default")
      (node (ref "Q2") (pin "4") (pinfunction "G_4") (pintype "passive"))
      (node (ref "R7") (pin "2") (pinfunction "2_2") (pintype "passive"))
    )
    (net (code "76") (name "Net-(Q3-G)") (class "Default")
      (node (ref "Q3") (pin "4") (pinfunction "G_4") (pintype "passive"))
      (node (ref "R6") (pin "2") (pinfunction "2_2") (pintype "passive"))
    )
    (net (code "77") (name "Net-(Q4-G)") (class "Default")
      (node (ref "Q4") (pin "4") (pinfunction "G_4") (pintype "passive"))
      (node (ref "R13") (pin "2") (pinfunction "2_2") (pintype "passive"))
    )
    (net (code "78") (name "Net-(Q5-G)") (class "Default")
      (node (ref "Q5") (pin "4") (pinfunction "G_4") (pintype "passive"))
      (node (ref "R14") (pin "2") (pinfunction "2_2") (pintype "passive"))
    )
    (net (code "79") (name "Net-(Q6-G)") (class "Default")
      (node (ref "Q6") (pin "4") (pinfunction "G_4") (pintype "passive"))
      (node (ref "R15") (pin "2") (pinfunction "2_2") (pintype "passive"))
    )
    (net (code "80") (name "Net-(U1A-BOOT0)") (class "Default")
      (node (ref "R31") (pin "2") (pinfunction "2_2") (pintype "passive"))
      (node (ref "U1") (pin "60") (pinfunction "BOOT0_60") (pintype "passive"))
    )
    (net (code "81") (name "Net-(U1A-PB2-BOOT1(PB2))") (class "Default")
      (node (ref "R28") (pin "1") (pinfunction "1_1") (pintype "passive"))
      (node (ref "U1") (pin "28") (pinfunction "PB2-BOOT1(PB2)_28") (pintype "passive"))
    )
    (net (code "82") (name "Net-(U1A-VCAP_1)") (class "Default")
      (node (ref "C55") (pin "2") (pinfunction "2_2") (pintype "passive"))
      (node (ref "U1") (pin "31") (pinfunction "VCAP_1_31") (pintype "passive"))
    )
    (net (code "83") (name "Net-(U1A-VCAP_2)") (class "Default")
      (node (ref "C56") (pin "2") (pinfunction "2_2") (pintype "passive"))
      (node (ref "U1") (pin "47") (pinfunction "VCAP_2_47") (pintype "passive"))
    )
    (net (code "84") (name "POWER_BUCK") (class "Default")
      (node (ref "C4") (pin "1") (pinfunction "1_1") (pintype "passive"))
      (node (ref "IC1") (pin "2") (pinfunction "VIN_2") (pintype "passive"))
      (node (ref "IC1") (pin "3") (pinfunction "EN_3") (pintype "passive"))
      (node (ref "L1") (pin "2") (pinfunction "2_2") (pintype "passive"))
    )
    (net (code "85") (name "POWER_IN") (class "Default")
      (node (ref "C21") (pin "2") (pinfunction "2_2") (pintype "passive"))
      (node (ref "D2") (pin "2") (pinfunction "2_2") (pintype "passive"))
      (node (ref "J1") (pin "1") (pintype "passive"))
      (node (ref "Q7") (pin "5") (pinfunction "D_5") (pintype "passive"))
      (node (ref "Q7") (pin "6") (pinfunction "D_6") (pintype "passive"))
      (node (ref "Q7") (pin "7") (pinfunction "D_7") (pintype "passive"))
      (node (ref "Q7") (pin "8") (pinfunction "D_8") (pintype "passive"))
      (node (ref "Q7") (pin "9") (pinfunction "D_9") (pintype "passive"))
      (node (ref "R24") (pin "2") (pinfunction "2_2") (pintype "passive"))
      (node (ref "R26") (pin "2") (pinfunction "2_2") (pintype "passive"))
    )
    (net (code "86") (name "POWER_LOAD") (class "Default")
      (node (ref "C34") (pin "2") (pinfunction "2_2") (pintype "passive"))
      (node (ref "C35") (pin "2") (pinfunction "2_2") (pintype "passive"))
      (node (ref "C36") (pin "1") (pinfunction "1_1") (pintype "passive"))
      (node (ref "C37") (pin "1") (pinfunction "1_1") (pintype "passive"))
      (node (ref "C38") (pin "1") (pinfunction "1_1") (pintype "passive"))
      (node (ref "C39") (pin "1") (pinfunction "1_1") (pintype "passive"))
      (node (ref "C5") (pin "2") (pinfunction "2_2") (pintype "passive"))
      (node (ref "C8") (pin "1") (pinfunction "1_1") (pintype "passive"))
      (node (ref "IC3") (pin "29") (pinfunction "PVDD1_29") (pintype "passive"))
      (node (ref "L1") (pin "1") (pinfunction "1_1") (pintype "passive"))
      (node (ref "Q1") (pin "5") (pinfunction "D_5") (pintype "passive"))
      (node (ref "Q1") (pin "6") (pinfunction "D_6") (pintype "passive"))
      (node (ref "Q1") (pin "7") (pinfunction "D_7") (pintype "passive"))
      (node (ref "Q1") (pin "8") (pinfunction "D_8") (pintype "passive"))
      (node (ref "Q1") (pin "9") (pinfunction "D_9") (pintype "passive"))
      (node (ref "Q2") (pin "5") (pinfunction "D_5") (pintype "passive"))
      (node (ref "Q2") (pin "6") (pinfunction "D_6") (pintype "passive"))
      (node (ref "Q2") (pin "7") (pinfunction "D_7") (pintype "passive"))
      (node (ref "Q2") (pin "8") (pinfunction "D_8") (pintype "passive"))
      (node (ref "Q2") (pin "9") (pinfunction "D_9") (pintype "passive"))
      (node (ref "Q3") (pin "5") (pinfunction "D_5") (pintype "passive"))
      (node (ref "Q3") (pin "6") (pinfunction "D_6") (pintype "passive"))
      (node (ref "Q3") (pin "7") (pinfunction "D_7") (pintype "passive"))
      (node (ref "Q3") (pin "8") (pinfunction "D_8") (pintype "passive"))
      (node (ref "Q3") (pin "9") (pinfunction "D_9") (pintype "passive"))
      (node (ref "Q8") (pin "5") (pinfunction "D_5") (pintype "passive"))
      (node (ref "Q8") (pin "6") (pinfunction "D_6") (pintype "passive"))
      (node (ref "Q8") (pin "7") (pinfunction "D_7") (pintype "passive"))
      (node (ref "Q8") (pin "8") (pinfunction "D_8") (pintype "passive"))
      (node (ref "Q8") (pin "9") (pinfunction "D_9") (pintype "passive"))
      (node (ref "R1") (pin "2") (pinfunction "2_2") (pintype "passive"))
      (node (ref "R2") (pin "2") (pinfunction "2_2") (pintype "passive"))
      (node (ref "R3") (pin "2") (pinfunction "2_2") (pintype "passive"))
    )
    (net (code "87") (name "V_5V") (class "Default")
      (node (ref "C22") (pin "2") (pinfunction "2_2") (pintype "passive"))
      (node (ref "C48") (pin "2") (pinfunction "2_2") (pintype "passive"))
      (node (ref "C49") (pin "2") (pinfunction "2_2") (pintype "passive"))
      (node (ref "C6") (pin "2") (pinfunction "2_2") (pintype "passive"))
      (node (ref "C7") (pin "2") (pinfunction "2_2") (pintype "passive"))
      (node (ref "IC2") (pin "1") (pinfunction "VIN_1") (pintype "passive"))
      (node (ref "IC5") (pin "3") (pinfunction "VCC_3") (pintype "passive"))
      (node (ref "L2") (pin "2") (pinfunction "2_2") (pintype "passive"))
      (node (ref "R19") (pin "2") (pinfunction "2_2") (pintype "passive"))
      (node (ref "R4") (pin "2") (pinfunction "2_2") (pintype "passive"))
    )
    (net (code "88") (name "unconnected-(IC2-NC-Pad4)") (class "Default")
      (node (ref "IC2") (pin "4") (pinfunction "NC_4") (pintype "passive+no_connect"))
    )
    (net (code "89") (name "unconnected-(IC3-BST_BK-Pad52)") (class "Default")
      (node (ref "IC3") (pin "52") (pinfunction "BST_BK_52") (pintype "passive+no_connect"))
    )
    (net (code "90") (name "unconnected-(IC3-COMP-Pad2)") (class "Default")
      (node (ref "IC3") (pin "2") (pinfunction "COMP_2") (pintype "passive+no_connect"))
    )
    (net (code "91") (name "unconnected-(IC3-PH-Pad50)") (class "Default")
      (node (ref "IC3") (pin "50") (pinfunction "PH_50") (pintype "passive+no_connect"))
    )
    (net (code "92") (name "unconnected-(IC3-PH-Pad51)") (class "Default")
      (node (ref "IC3") (pin "51") (pinfunction "PH_51") (pintype "passive+no_connect"))
    )
    (net (code "93") (name "unconnected-(IC3-PVDD2-Pad53)") (class "Default")
      (node (ref "IC3") (pin "53") (pinfunction "PVDD2_53") (pintype "passive+no_connect"))
    )
    (net (code "94") (name "unconnected-(IC3-PVDD2-Pad54)") (class "Default")
      (node (ref "IC3") (pin "54") (pinfunction "PVDD2_54") (pintype "passive+no_connect"))
    )
    (net (code "95") (name "unconnected-(IC3-PWRGD-Pad4)") (class "Default")
      (node (ref "IC3") (pin "4") (pinfunction "PWRGD_4") (pintype "passive+no_connect"))
    )
    (net (code "96") (name "unconnected-(IC3-RT_CLK-Pad1)") (class "Default")
      (node (ref "IC3") (pin "1") (pinfunction "RT_CLK_1") (pintype "passive+no_connect"))
    )
    (net (code "97") (name "unconnected-(IC3-SS_TR-Pad56)") (class "Default")
      (node (ref "IC3") (pin "56") (pinfunction "SS_TR_56") (pintype "passive+no_connect"))
    )
    (net (code "98") (name "unconnected-(IC3-VSENSE-Pad3)") (class "Default")
      (node (ref "IC3") (pin "3") (pinfunction "VSENSE_3") (pintype "passive+no_connect"))
    )
    (net (code "99") (name "unconnected-(IC4-N.C-Pad3)") (class "Default")
      (node (ref "IC4") (pin "3") (pinfunction "N.C_3") (pintype "passive+no_connect"))
    )
    (net (code "100") (name "unconnected-(U1A-PA2-Pad16)") (class "Default")
      (node (ref "U1") (pin "16") (pinfunction "PA2_16") (pintype "passive+no_connect"))
    )
    (net (code "101") (name "unconnected-(U1A-PA3-Pad17)") (class "Default")
      (node (ref "U1") (pin "17") (pinfunction "PA3_17") (pintype "passive+no_connect"))
    )
    (net (code "102") (name "unconnected-(U1A-PA5-Pad21)") (class "Default")
      (node (ref "U1") (pin "21") (pinfunction "PA5_21") (pintype "passive+no_connect"))
    )
    (net (code "103") (name "unconnected-(U1A-PA7-Pad23)") (class "Default")
      (node (ref "U1") (pin "23") (pinfunction "PA7_23") (pintype "passive+no_connect"))
    )
    (net (code "104") (name "unconnected-(U1A-PA11-Pad44)") (class "Default")
      (node (ref "U1") (pin "44") (pinfunction "PA11_44") (pintype "passive+no_connect"))
    )
    (net (code "105") (name "unconnected-(U1A-PA12-Pad45)") (class "Default")
      (node (ref "U1") (pin "45") (pinfunction "PA12_45") (pintype "passive+no_connect"))
    )
    (net (code "106") (name "unconnected-(U1A-PA15(JTDI)-Pad50)") (class "Default")
      (node (ref "U1") (pin "50") (pinfunction "PA15(JTDI)_50") (pintype "passive+no_connect"))
    )
    (net (code "107") (name "unconnected-(U1A-PB0-Pad26)") (class "Default")
      (node (ref "U1") (pin "26") (pinfunction "PB0_26") (pintype "passive+no_connect"))
    )
    (net (code "108") (name "unconnected-(U1A-PB1-Pad27)") (class "Default")
      (node (ref "U1") (pin "27") (pinfunction "PB1_27") (pintype "passive+no_connect"))
    )
    (net (code "109") (name "unconnected-(U1A-PB3(JTDOTRACESWO)-Pad55)") (class "Default")
      (node (ref "U1") (pin "55") (pinfunction "PB3(JTDOTRACESWO)_55") (pintype "passive+no_connect"))
    )
    (net (code "110") (name "unconnected-(U1A-PB4(NJTRST)-Pad56)") (class "Default")
      (node (ref "U1") (pin "56") (pinfunction "PB4(NJTRST)_56") (pintype "passive+no_connect"))
    )
    (net (code "111") (name "unconnected-(U1A-PB5-Pad57)") (class "Default")
      (node (ref "U1") (pin "57") (pinfunction "PB5_57") (pintype "passive+no_connect"))
    )
    (net (code "112") (name "unconnected-(U1A-PB6-Pad58)") (class "Default")
      (node (ref "U1") (pin "58") (pinfunction "PB6_58") (pintype "passive+no_connect"))
    )
    (net (code "113") (name "unconnected-(U1A-PB7-Pad59)") (class "Default")
      (node (ref "U1") (pin "59") (pinfunction "PB7_59") (pintype "passive+no_connect"))
    )
    (net (code "114") (name "unconnected-(U1A-PB10-Pad29)") (class "Default")
      (node (ref "U1") (pin "29") (pinfunction "PB10_29") (pintype "passive+no_connect"))
    )
    (net (code "115") (name "unconnected-(U1A-PB11-Pad30)") (class "Default")
      (node (ref "U1") (pin "30") (pinfunction "PB11_30") (pintype "passive+no_connect"))
    )
    (net (code "116") (name "unconnected-(U1A-PB12-Pad33)") (class "Default")
      (node (ref "U1") (pin "33") (pinfunction "PB12_33") (pintype "passive+no_connect"))
    )
    (net (code "117") (name "unconnected-(U1A-PC0-Pad8)") (class "Default")
      (node (ref "U1") (pin "8") (pinfunction "PC0_8") (pintype "passive+no_connect"))
    )
    (net (code "118") (name "unconnected-(U1A-PC1-Pad9)") (class "Default")
      (node (ref "U1") (pin "9") (pinfunction "PC1_9") (pintype "passive+no_connect"))
    )
    (net (code "119") (name "unconnected-(U1A-PC4-Pad24)") (class "Default")
      (node (ref "U1") (pin "24") (pinfunction "PC4_24") (pintype "passive+no_connect"))
    )
    (net (code "120") (name "unconnected-(U1A-PC5-Pad25)") (class "Default")
      (node (ref "U1") (pin "25") (pinfunction "PC5_25") (pintype "passive+no_connect"))
    )
    (net (code "121") (name "unconnected-(U1A-PC6-Pad37)") (class "Default")
      (node (ref "U1") (pin "37") (pinfunction "PC6_37") (pintype "passive+no_connect"))
    )
    (net (code "122") (name "unconnected-(U1A-PC7-Pad38)") (class "Default")
      (node (ref "U1") (pin "38") (pinfunction "PC7_38") (pintype "passive+no_connect"))
    )
    (net (code "123") (name "unconnected-(U1A-PC8-Pad39)") (class "Default")
      (node (ref "U1") (pin "39") (pinfunction "PC8_39") (pintype "passive+no_connect"))
    )
    (net (code "124") (name "unconnected-(U1A-PC9-Pad40)") (class "Default")
      (node (ref "U1") (pin "40") (pinfunction "PC9_40") (pintype "passive+no_connect"))
    )
    (net (code "125") (name "unconnected-(U1A-PC13-Pad2)") (class "Default")
      (node (ref "U1") (pin "2") (pinfunction "PC13_2") (pintype "passive+no_connect"))
    )
    (net (code "126") (name "unconnected-(U1A-PC14-OSC32_IN(PC14)-Pad3)") (class "Default")
      (node (ref "U1") (pin "3") (pinfunction "PC14-OSC32_IN(PC14)_3") (pintype "passive+no_connect"))
    )
    (net (code "127") (name "unconnected-(U1A-PC15-OSC32_OUT(PC15)-Pad4)") (class "Default")
      (node (ref "U1") (pin "4") (pinfunction "PC15-OSC32_OUT(PC15)_4") (pintype "passive+no_connect"))
    )
    (net (code "128") (name "unconnected-(U1A-PD2-Pad54)") (class "Default")
      (node (ref "U1") (pin "54") (pinfunction "PD2_54") (pintype "passive+no_connect"))
    )
  )
)
